# VALVEBOARD_ValveDrive2.net
KiCad netlist of a schematic drawn in Altium Designer
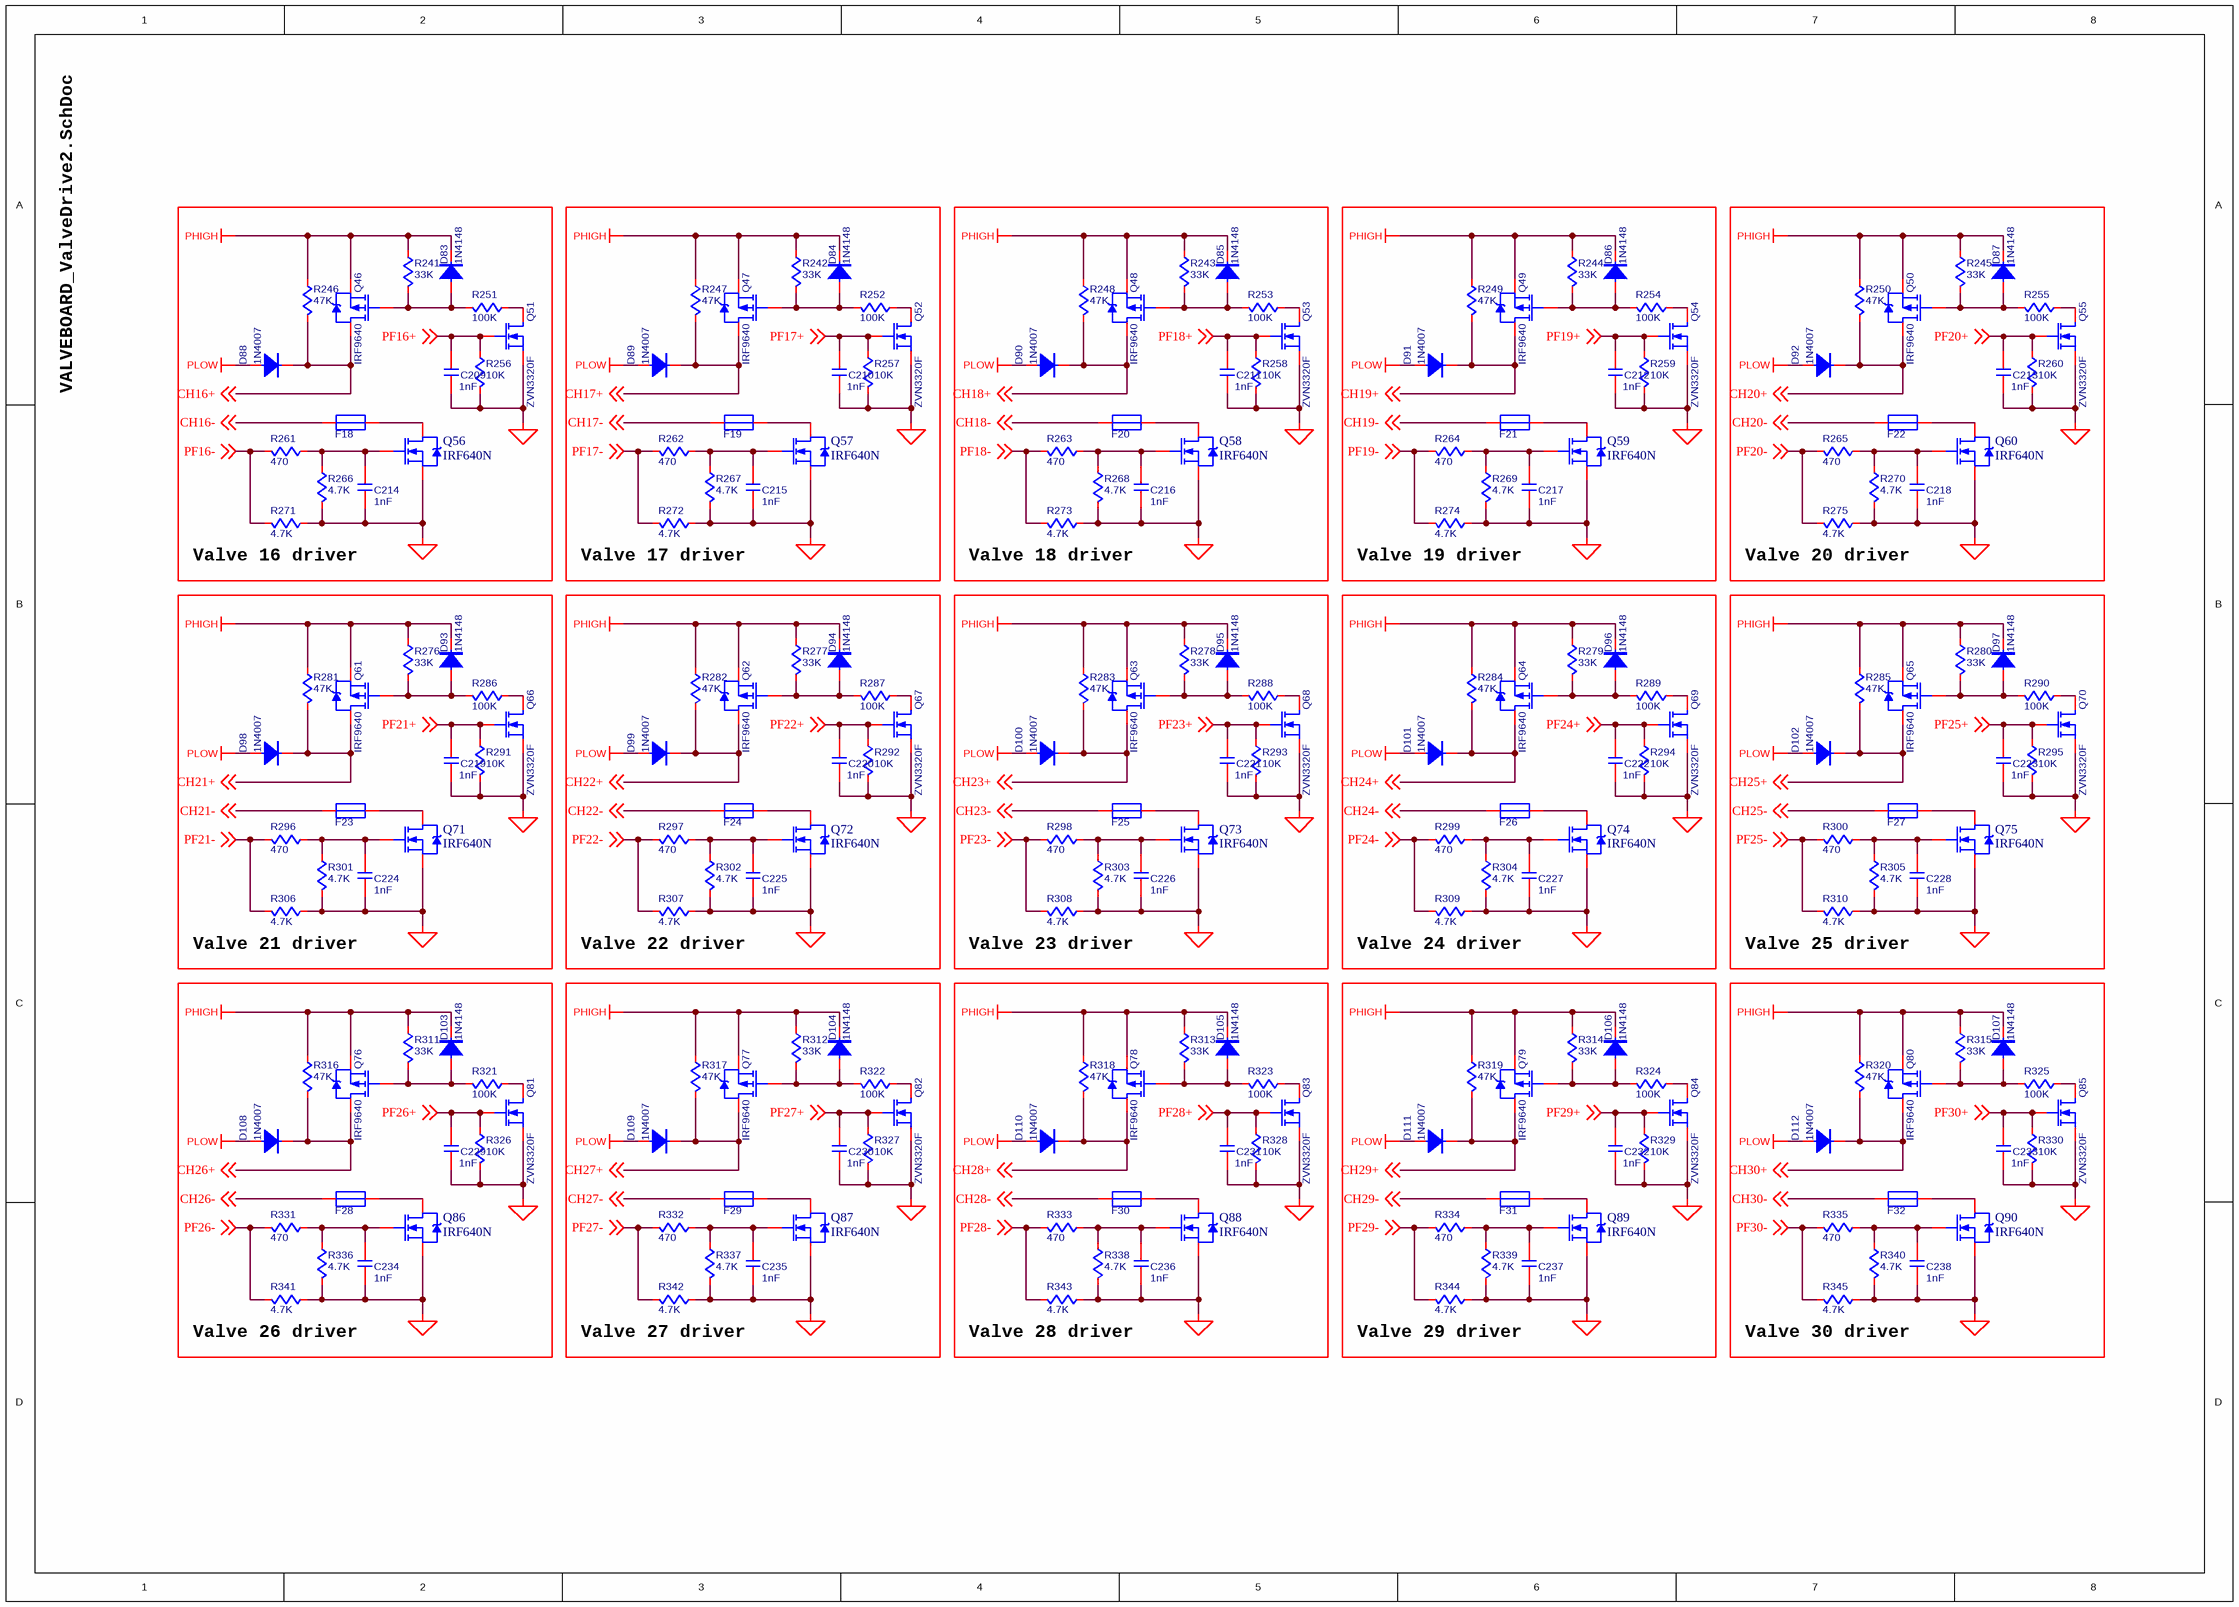
[diagram p0: VALVEBOARD_ValveDrive2.SchDoc]

(export (version "E")
  (design (tool "Eeschema 10.0.6"))
  (components
    (comp (ref "C209")
      (value "1nF")
      (footprint "zynq:C0603")
      (fields (field (name "VOLTAGE") "25V") (field (name "Comment") "C-NOMO"))
      (libsource (lib "zynq") (part "C-NOMO"))
    )
    (comp (ref "C210")
      (value "1nF")
      (footprint "zynq:C0603")
      (fields (field (name "VOLTAGE") "25V") (field (name "Comment") "C-NOMO"))
      (libsource (lib "zynq") (part "C-NOMO"))
    )
    (comp (ref "C211")
      (value "1nF")
      (footprint "zynq:C0603")
      (fields (field (name "VOLTAGE") "25V") (field (name "Comment") "C-NOMO"))
      (libsource (lib "zynq") (part "C-NOMO"))
    )
    (comp (ref "C212")
      (value "1nF")
      (footprint "zynq:C0603")
      (fields (field (name "VOLTAGE") "25V") (field (name "Comment") "C-NOMO"))
      (libsource (lib "zynq") (part "C-NOMO"))
    )
    (comp (ref "C213")
      (value "1nF")
      (footprint "zynq:C0603")
      (fields (field (name "VOLTAGE") "25V") (field (name "Comment") "C-NOMO"))
      (libsource (lib "zynq") (part "C-NOMO"))
    )
    (comp (ref "C214")
      (value "1nF")
      (footprint "zynq:C0603")
      (fields (field (name "VOLTAGE") "25V") (field (name "Comment") "C-NOMO"))
      (libsource (lib "zynq") (part "C-NOMO"))
    )
    (comp (ref "C215")
      (value "1nF")
      (footprint "zynq:C0603")
      (fields (field (name "VOLTAGE") "25V") (field (name "Comment") "C-NOMO"))
      (libsource (lib "zynq") (part "C-NOMO"))
    )
    (comp (ref "C216")
      (value "1nF")
      (footprint "zynq:C0603")
      (fields (field (name "VOLTAGE") "25V") (field (name "Comment") "C-NOMO"))
      (libsource (lib "zynq") (part "C-NOMO"))
    )
    (comp (ref "C217")
      (value "1nF")
      (footprint "zynq:C0603")
      (fields (field (name "VOLTAGE") "25V") (field (name "Comment") "C-NOMO"))
      (libsource (lib "zynq") (part "C-NOMO"))
    )
    (comp (ref "C218")
      (value "1nF")
      (footprint "zynq:C0603")
      (fields (field (name "VOLTAGE") "25V") (field (name "Comment") "C-NOMO"))
      (libsource (lib "zynq") (part "C-NOMO"))
    )
    (comp (ref "C219")
      (value "1nF")
      (footprint "zynq:C0603")
      (fields (field (name "VOLTAGE") "25V") (field (name "Comment") "C-NOMO"))
      (libsource (lib "zynq") (part "C-NOMO"))
    )
    (comp (ref "C220")
      (value "1nF")
      (footprint "zynq:C0603")
      (fields (field (name "VOLTAGE") "25V") (field (name "Comment") "C-NOMO"))
      (libsource (lib "zynq") (part "C-NOMO"))
    )
    (comp (ref "C221")
      (value "1nF")
      (footprint "zynq:C0603")
      (fields (field (name "VOLTAGE") "25V") (field (name "Comment") "C-NOMO"))
      (libsource (lib "zynq") (part "C-NOMO"))
    )
    (comp (ref "C222")
      (value "1nF")
      (footprint "zynq:C0603")
      (fields (field (name "VOLTAGE") "25V") (field (name "Comment") "C-NOMO"))
      (libsource (lib "zynq") (part "C-NOMO"))
    )
    (comp (ref "C223")
      (value "1nF")
      (footprint "zynq:C0603")
      (fields (field (name "VOLTAGE") "25V") (field (name "Comment") "C-NOMO"))
      (libsource (lib "zynq") (part "C-NOMO"))
    )
    (comp (ref "C224")
      (value "1nF")
      (footprint "zynq:C0603")
      (fields (field (name "VOLTAGE") "25V") (field (name "Comment") "C-NOMO"))
      (libsource (lib "zynq") (part "C-NOMO"))
    )
    (comp (ref "C225")
      (value "1nF")
      (footprint "zynq:C0603")
      (fields (field (name "VOLTAGE") "25V") (field (name "Comment") "C-NOMO"))
      (libsource (lib "zynq") (part "C-NOMO"))
    )
    (comp (ref "C226")
      (value "1nF")
      (footprint "zynq:C0603")
      (fields (field (name "VOLTAGE") "25V") (field (name "Comment") "C-NOMO"))
      (libsource (lib "zynq") (part "C-NOMO"))
    )
    (comp (ref "C227")
      (value "1nF")
      (footprint "zynq:C0603")
      (fields (field (name "VOLTAGE") "25V") (field (name "Comment") "C-NOMO"))
      (libsource (lib "zynq") (part "C-NOMO"))
    )
    (comp (ref "C228")
      (value "1nF")
      (footprint "zynq:C0603")
      (fields (field (name "VOLTAGE") "25V") (field (name "Comment") "C-NOMO"))
      (libsource (lib "zynq") (part "C-NOMO"))
    )
    (comp (ref "C229")
      (value "1nF")
      (footprint "zynq:C0603")
      (fields (field (name "VOLTAGE") "25V") (field (name "Comment") "C-NOMO"))
      (libsource (lib "zynq") (part "C-NOMO"))
    )
    (comp (ref "C230")
      (value "1nF")
      (footprint "zynq:C0603")
      (fields (field (name "VOLTAGE") "25V") (field (name "Comment") "C-NOMO"))
      (libsource (lib "zynq") (part "C-NOMO"))
    )
    (comp (ref "C231")
      (value "1nF")
      (footprint "zynq:C0603")
      (fields (field (name "VOLTAGE") "25V") (field (name "Comment") "C-NOMO"))
      (libsource (lib "zynq") (part "C-NOMO"))
    )
    (comp (ref "C232")
      (value "1nF")
      (footprint "zynq:C0603")
      (fields (field (name "VOLTAGE") "25V") (field (name "Comment") "C-NOMO"))
      (libsource (lib "zynq") (part "C-NOMO"))
    )
    (comp (ref "C233")
      (value "1nF")
      (footprint "zynq:C0603")
      (fields (field (name "VOLTAGE") "25V") (field (name "Comment") "C-NOMO"))
      (libsource (lib "zynq") (part "C-NOMO"))
    )
    (comp (ref "C234")
      (value "1nF")
      (footprint "zynq:C0603")
      (fields (field (name "VOLTAGE") "25V") (field (name "Comment") "C-NOMO"))
      (libsource (lib "zynq") (part "C-NOMO"))
    )
    (comp (ref "C235")
      (value "1nF")
      (footprint "zynq:C0603")
      (fields (field (name "VOLTAGE") "25V") (field (name "Comment") "C-NOMO"))
      (libsource (lib "zynq") (part "C-NOMO"))
    )
    (comp (ref "C236")
      (value "1nF")
      (footprint "zynq:C0603")
      (fields (field (name "VOLTAGE") "25V") (field (name "Comment") "C-NOMO"))
      (libsource (lib "zynq") (part "C-NOMO"))
    )
    (comp (ref "C237")
      (value "1nF")
      (footprint "zynq:C0603")
      (fields (field (name "VOLTAGE") "25V") (field (name "Comment") "C-NOMO"))
      (libsource (lib "zynq") (part "C-NOMO"))
    )
    (comp (ref "C238")
      (value "1nF")
      (footprint "zynq:C0603")
      (fields (field (name "VOLTAGE") "25V") (field (name "Comment") "C-NOMO"))
      (libsource (lib "zynq") (part "C-NOMO"))
    )
    (comp (ref "D83") (value "1N4148") (footprint "sod-123") (libsource (lib "") (part "DIOD1_1")))
    (comp (ref "D84") (value "1N4148") (footprint "sod-123") (libsource (lib "") (part "DIOD1_1")))
    (comp (ref "D85") (value "1N4148") (footprint "sod-123") (libsource (lib "") (part "DIOD1_1")))
    (comp (ref "D86") (value "1N4148") (footprint "sod-123") (libsource (lib "") (part "DIOD1_1")))
    (comp (ref "D87") (value "1N4148") (footprint "sod-123") (libsource (lib "") (part "DIOD1_1")))
    (comp (ref "D88") (value "1N4007") (footprint "zynq:1N4148") (libsource (lib "zynq") (part "DIOD1")))
    (comp (ref "D89") (value "1N4007") (footprint "zynq:1N4148") (libsource (lib "zynq") (part "DIOD1")))
    (comp (ref "D90") (value "1N4007") (footprint "zynq:1N4148") (libsource (lib "zynq") (part "DIOD1")))
    (comp (ref "D91") (value "1N4007") (footprint "zynq:1N4148") (libsource (lib "zynq") (part "DIOD1")))
    (comp (ref "D92") (value "1N4007") (footprint "zynq:1N4148") (libsource (lib "zynq") (part "DIOD1")))
    (comp (ref "D93") (value "1N4148") (footprint "sod-123") (libsource (lib "") (part "DIOD1_1")))
    (comp (ref "D94") (value "1N4148") (footprint "sod-123") (libsource (lib "") (part "DIOD1_1")))
    (comp (ref "D95") (value "1N4148") (footprint "sod-123") (libsource (lib "") (part "DIOD1_1")))
    (comp (ref "D96") (value "1N4148") (footprint "sod-123") (libsource (lib "") (part "DIOD1_1")))
    (comp (ref "D97") (value "1N4148") (footprint "sod-123") (libsource (lib "") (part "DIOD1_1")))
    (comp (ref "D98") (value "1N4007") (footprint "zynq:1N4148") (libsource (lib "zynq") (part "DIOD1")))
    (comp (ref "D99") (value "1N4007") (footprint "zynq:1N4148") (libsource (lib "zynq") (part "DIOD1")))
    (comp (ref "D100") (value "1N4007") (footprint "zynq:1N4148") (libsource (lib "zynq") (part "DIOD1")))
    (comp (ref "D101") (value "1N4007") (footprint "zynq:1N4148") (libsource (lib "zynq") (part "DIOD1")))
    (comp (ref "D102") (value "1N4007") (footprint "zynq:1N4148") (libsource (lib "zynq") (part "DIOD1")))
    (comp (ref "D103") (value "1N4148") (footprint "sod-123") (libsource (lib "") (part "DIOD1_1")))
    (comp (ref "D104") (value "1N4148") (footprint "sod-123") (libsource (lib "") (part "DIOD1_1")))
    (comp (ref "D105") (value "1N4148") (footprint "sod-123") (libsource (lib "") (part "DIOD1_1")))
    (comp (ref "D106") (value "1N4148") (footprint "sod-123") (libsource (lib "") (part "DIOD1_1")))
    (comp (ref "D107") (value "1N4148") (footprint "SOD-123") (libsource (lib "") (part "DIOD1_1")))
    (comp (ref "D108") (value "1N4007") (footprint "zynq:1N4148") (libsource (lib "zynq") (part "DIOD1")))
    (comp (ref "D109") (value "1N4007") (footprint "zynq:1N4148") (libsource (lib "zynq") (part "DIOD1")))
    (comp (ref "D110") (value "1N4007") (footprint "zynq:1N4148") (libsource (lib "zynq") (part "DIOD1")))
    (comp (ref "D111") (value "1N4007") (footprint "zynq:1N4148") (libsource (lib "zynq") (part "DIOD1")))
    (comp (ref "D112") (value "1N4007") (footprint "zynq:1N4148") (libsource (lib "zynq") (part "DIOD1")))
    (comp (ref "F18") (value "F50") (footprint "zynq:F-TH") (libsource (lib "zynq") (part "F50")))
    (comp (ref "F19") (value "F50") (footprint "zynq:F-TH") (libsource (lib "zynq") (part "F50")))
    (comp (ref "F20") (value "F50") (footprint "zynq:F-TH") (libsource (lib "zynq") (part "F50")))
    (comp (ref "F21") (value "F50") (footprint "zynq:F-TH") (libsource (lib "zynq") (part "F50")))
    (comp (ref "F22") (value "F50") (footprint "zynq:F-TH") (libsource (lib "zynq") (part "F50")))
    (comp (ref "F23") (value "F50") (footprint "zynq:F-TH") (libsource (lib "zynq") (part "F50")))
    (comp (ref "F24") (value "F50") (footprint "zynq:F-TH") (libsource (lib "zynq") (part "F50")))
    (comp (ref "F25") (value "F50") (footprint "zynq:F-TH") (libsource (lib "zynq") (part "F50")))
    (comp (ref "F26") (value "F50") (footprint "zynq:F-TH") (libsource (lib "zynq") (part "F50")))
    (comp (ref "F27") (value "F50") (footprint "zynq:F-TH") (libsource (lib "zynq") (part "F50")))
    (comp (ref "F28") (value "F50") (footprint "zynq:F-TH") (libsource (lib "zynq") (part "F50")))
    (comp (ref "F29") (value "F50") (footprint "zynq:F-TH") (libsource (lib "zynq") (part "F50")))
    (comp (ref "F30") (value "F50") (footprint "zynq:F-TH") (libsource (lib "zynq") (part "F50")))
    (comp (ref "F31") (value "F50") (footprint "zynq:F-TH") (libsource (lib "zynq") (part "F50")))
    (comp (ref "F32") (value "F50") (footprint "zynq:F-TH") (libsource (lib "zynq") (part "F50")))
    (comp (ref "Q46")
      (value "IRF9640")
      (footprint "TO-220AB")
      (description "P-Channel Power MOSFET")
      (fields (field (name "PUBLISHER") "Altium Limited"))
      (libsource (lib "zynq") (part "IRF9640"))
    )
    (comp (ref "Q47")
      (value "IRF9640")
      (footprint "TO-220AB")
      (description "P-Channel Power MOSFET")
      (fields (field (name "PUBLISHER") "Altium Limited"))
      (libsource (lib "zynq") (part "IRF9640"))
    )
    (comp (ref "Q48")
      (value "IRF9640")
      (footprint "TO-220AB")
      (description "P-Channel Power MOSFET")
      (fields (field (name "PUBLISHER") "Altium Limited"))
      (libsource (lib "zynq") (part "IRF9640"))
    )
    (comp (ref "Q49")
      (value "IRF9640")
      (footprint "TO-220AB")
      (description "P-Channel Power MOSFET")
      (fields (field (name "PUBLISHER") "Altium Limited"))
      (libsource (lib "zynq") (part "IRF9640"))
    )
    (comp (ref "Q50")
      (value "IRF9640")
      (footprint "TO-220AB")
      (description "P-Channel Power MOSFET")
      (fields (field (name "PUBLISHER") "Altium Limited"))
      (libsource (lib "zynq") (part "IRF9640"))
    )
    (comp (ref "Q51")
      (value "ZVN3320F")
      (footprint "zynq:ZVN3320F")
      (description "N-Channel MOSFET")
      (fields (field (name "PUBLISHER") "Altium Limited"))
      (libsource (lib "zynq") (part "ZVN3320F"))
    )
    (comp (ref "Q52")
      (value "ZVN3320F")
      (footprint "zynq:ZVN3320F")
      (description "N-Channel MOSFET")
      (fields (field (name "PUBLISHER") "Altium Limited"))
      (libsource (lib "zynq") (part "ZVN3320F"))
    )
    (comp (ref "Q53")
      (value "ZVN3320F")
      (footprint "zynq:ZVN3320F")
      (description "N-Channel MOSFET")
      (fields (field (name "PUBLISHER") "Altium Limited"))
      (libsource (lib "zynq") (part "ZVN3320F"))
    )
    (comp (ref "Q54")
      (value "ZVN3320F")
      (footprint "zynq:ZVN3320F")
      (description "N-Channel MOSFET")
      (fields (field (name "PUBLISHER") "Altium Limited"))
      (libsource (lib "zynq") (part "ZVN3320F"))
    )
    (comp (ref "Q55")
      (value "ZVN3320F")
      (footprint "zynq:ZVN3320F")
      (description "N-Channel MOSFET")
      (fields (field (name "PUBLISHER") "Altium Limited"))
      (libsource (lib "zynq") (part "ZVN3320F"))
    )
    (comp (ref "Q56")
      (value "IRF640N")
      (footprint "zynq:TO-220AB")
      (description "N-Channel Power MOSFET")
      (fields (field (name "PUBLISHER") "Altium Limited"))
      (libsource (lib "zynq") (part "IRF640N"))
    )
    (comp (ref "Q57")
      (value "IRF640N")
      (footprint "zynq:TO-220AB")
      (description "N-Channel Power MOSFET")
      (fields (field (name "PUBLISHER") "Altium Limited"))
      (libsource (lib "zynq") (part "IRF640N"))
    )
    (comp (ref "Q58")
      (value "IRF640N")
      (footprint "zynq:TO-220AB")
      (description "N-Channel Power MOSFET")
      (fields (field (name "PUBLISHER") "Altium Limited"))
      (libsource (lib "zynq") (part "IRF640N"))
    )
    (comp (ref "Q59")
      (value "IRF640N")
      (footprint "zynq:TO-220AB")
      (description "N-Channel Power MOSFET")
      (fields (field (name "PUBLISHER") "Altium Limited"))
      (libsource (lib "zynq") (part "IRF640N"))
    )
    (comp (ref "Q60")
      (value "IRF640N")
      (footprint "zynq:TO-220AB")
      (description "N-Channel Power MOSFET")
      (fields (field (name "PUBLISHER") "Altium Limited"))
      (libsource (lib "zynq") (part "IRF640N"))
    )
    (comp (ref "Q61")
      (value "IRF9640")
      (footprint "TO-220AB")
      (description "P-Channel Power MOSFET")
      (fields (field (name "PUBLISHER") "Altium Limited"))
      (libsource (lib "zynq") (part "IRF9640"))
    )
    (comp (ref "Q62")
      (value "IRF9640")
      (footprint "TO-220AB")
      (description "P-Channel Power MOSFET")
      (fields (field (name "PUBLISHER") "Altium Limited"))
      (libsource (lib "zynq") (part "IRF9640"))
    )
    (comp (ref "Q63")
      (value "IRF9640")
      (footprint "TO-220AB")
      (description "P-Channel Power MOSFET")
      (fields (field (name "PUBLISHER") "Altium Limited"))
      (libsource (lib "zynq") (part "IRF9640"))
    )
    (comp (ref "Q64")
      (value "IRF9640")
      (footprint "TO-220AB")
      (description "P-Channel Power MOSFET")
      (fields (field (name "PUBLISHER") "Altium Limited"))
      (libsource (lib "zynq") (part "IRF9640"))
    )
    (comp (ref "Q65")
      (value "IRF9640")
      (footprint "TO-220AB")
      (description "P-Channel Power MOSFET")
      (fields (field (name "PUBLISHER") "Altium Limited"))
      (libsource (lib "zynq") (part "IRF9640"))
    )
    (comp (ref "Q66")
      (value "ZVN3320F")
      (footprint "zynq:ZVN3320F")
      (description "N-Channel MOSFET")
      (fields (field (name "PUBLISHER") "Altium Limited"))
      (libsource (lib "zynq") (part "ZVN3320F"))
    )
    (comp (ref "Q67")
      (value "ZVN3320F")
      (footprint "zynq:ZVN3320F")
      (description "N-Channel MOSFET")
      (fields (field (name "PUBLISHER") "Altium Limited"))
      (libsource (lib "zynq") (part "ZVN3320F"))
    )
    (comp (ref "Q68")
      (value "ZVN3320F")
      (footprint "zynq:ZVN3320F")
      (description "N-Channel MOSFET")
      (fields (field (name "PUBLISHER") "Altium Limited"))
      (libsource (lib "zynq") (part "ZVN3320F"))
    )
    (comp (ref "Q69")
      (value "ZVN3320F")
      (footprint "zynq:ZVN3320F")
      (description "N-Channel MOSFET")
      (fields (field (name "PUBLISHER") "Altium Limited"))
      (libsource (lib "zynq") (part "ZVN3320F"))
    )
    (comp (ref "Q70")
      (value "ZVN3320F")
      (footprint "zynq:ZVN3320F")
      (description "N-Channel MOSFET")
      (fields (field (name "PUBLISHER") "Altium Limited"))
      (libsource (lib "zynq") (part "ZVN3320F"))
    )
    (comp (ref "Q71")
      (value "IRF640N")
      (footprint "zynq:TO-220AB")
      (description "N-Channel Power MOSFET")
      (fields (field (name "PUBLISHER") "Altium Limited"))
      (libsource (lib "zynq") (part "IRF640N"))
    )
    (comp (ref "Q72")
      (value "IRF640N")
      (footprint "zynq:TO-220AB")
      (description "N-Channel Power MOSFET")
      (fields (field (name "PUBLISHER") "Altium Limited"))
      (libsource (lib "zynq") (part "IRF640N"))
    )
    (comp (ref "Q73")
      (value "IRF640N")
      (footprint "zynq:TO-220AB")
      (description "N-Channel Power MOSFET")
      (fields (field (name "PUBLISHER") "Altium Limited"))
      (libsource (lib "zynq") (part "IRF640N"))
    )
    (comp (ref "Q74")
      (value "IRF640N")
      (footprint "zynq:TO-220AB")
      (description "N-Channel Power MOSFET")
      (fields (field (name "PUBLISHER") "Altium Limited"))
      (libsource (lib "zynq") (part "IRF640N"))
    )
    (comp (ref "Q75")
      (value "IRF640N")
      (footprint "zynq:TO-220AB")
      (description "N-Channel Power MOSFET")
      (fields (field (name "PUBLISHER") "Altium Limited"))
      (libsource (lib "zynq") (part "IRF640N"))
    )
    (comp (ref "Q76")
      (value "IRF9640")
      (footprint "TO-220AB")
      (description "P-Channel Power MOSFET")
      (fields (field (name "PUBLISHER") "Altium Limited"))
      (libsource (lib "zynq") (part "IRF9640"))
    )
    (comp (ref "Q77")
      (value "IRF9640")
      (footprint "TO-220AB")
      (description "P-Channel Power MOSFET")
      (fields (field (name "PUBLISHER") "Altium Limited"))
      (libsource (lib "zynq") (part "IRF9640"))
    )
    (comp (ref "Q78")
      (value "IRF9640")
      (footprint "TO-220AB")
      (description "P-Channel Power MOSFET")
      (fields (field (name "PUBLISHER") "Altium Limited"))
      (libsource (lib "zynq") (part "IRF9640"))
    )
    (comp (ref "Q79")
      (value "IRF9640")
      (footprint "TO-220AB")
      (description "P-Channel Power MOSFET")
      (fields (field (name "PUBLISHER") "Altium Limited"))
      (libsource (lib "zynq") (part "IRF9640"))
    )
    (comp (ref "Q80")
      (value "IRF9640")
      (footprint "TO-220AB")
      (description "P-Channel Power MOSFET")
      (fields (field (name "PUBLISHER") "Altium Limited"))
      (libsource (lib "zynq") (part "IRF9640"))
    )
    (comp (ref "Q81")
      (value "ZVN3320F")
      (footprint "zynq:ZVN3320F")
      (description "N-Channel MOSFET")
      (fields (field (name "PUBLISHER") "Altium Limited"))
      (libsource (lib "zynq") (part "ZVN3320F"))
    )
    (comp (ref "Q82")
      (value "ZVN3320F")
      (footprint "zynq:ZVN3320F")
      (description "N-Channel MOSFET")
      (fields (field (name "PUBLISHER") "Altium Limited"))
      (libsource (lib "zynq") (part "ZVN3320F"))
    )
    (comp (ref "Q83")
      (value "ZVN3320F")
      (footprint "zynq:ZVN3320F")
      (description "N-Channel MOSFET")
      (fields (field (name "PUBLISHER") "Altium Limited"))
      (libsource (lib "zynq") (part "ZVN3320F"))
    )
    (comp (ref "Q84")
      (value "ZVN3320F")
      (footprint "zynq:ZVN3320F")
      (description "N-Channel MOSFET")
      (fields (field (name "PUBLISHER") "Altium Limited"))
      (libsource (lib "zynq") (part "ZVN3320F"))
    )
    (comp (ref "Q85")
      (value "ZVN3320F")
      (footprint "zynq:ZVN3320F")
      (description "N-Channel MOSFET")
      (fields (field (name "PUBLISHER") "Altium Limited"))
      (libsource (lib "zynq") (part "ZVN3320F"))
    )
    (comp (ref "Q86")
      (value "IRF640N")
      (footprint "zynq:TO-220AB")
      (description "N-Channel Power MOSFET")
      (fields (field (name "PUBLISHER") "Altium Limited"))
      (libsource (lib "zynq") (part "IRF640N"))
    )
    (comp (ref "Q87")
      (value "IRF640N")
      (footprint "zynq:TO-220AB")
      (description "N-Channel Power MOSFET")
      (fields (field (name "PUBLISHER") "Altium Limited"))
      (libsource (lib "zynq") (part "IRF640N"))
    )
    (comp (ref "Q88")
      (value "IRF640N")
      (footprint "zynq:TO-220AB")
      (description "N-Channel Power MOSFET")
      (fields (field (name "PUBLISHER") "Altium Limited"))
      (libsource (lib "zynq") (part "IRF640N"))
    )
    (comp (ref "Q89")
      (value "IRF640N")
      (footprint "zynq:TO-220AB")
      (description "N-Channel Power MOSFET")
      (fields (field (name "PUBLISHER") "Altium Limited"))
      (libsource (lib "zynq") (part "IRF640N"))
    )
    (comp (ref "Q90")
      (value "IRF640N")
      (footprint "zynq:TO-220AB")
      (description "N-Channel Power MOSFET")
      (fields (field (name "PUBLISHER") "Altium Limited"))
      (libsource (lib "zynq") (part "IRF640N"))
    )
    (comp (ref "R241")
      (value "33K")
      (footprint "zynq:R0603")
      (fields (field (name "Comment") "R"))
      (libsource (lib "zynq") (part "R"))
    )
    (comp (ref "R242")
      (value "33K")
      (footprint "zynq:R0603")
      (fields (field (name "Comment") "R"))
      (libsource (lib "zynq") (part "R"))
    )
    (comp (ref "R243")
      (value "33K")
      (footprint "zynq:R0603")
      (fields (field (name "Comment") "R"))
      (libsource (lib "zynq") (part "R"))
    )
    (comp (ref "R244")
      (value "33K")
      (footprint "zynq:R0603")
      (fields (field (name "Comment") "R"))
      (libsource (lib "zynq") (part "R"))
    )
    (comp (ref "R245")
      (value "33K")
      (footprint "zynq:R0603")
      (fields (field (name "Comment") "R"))
      (libsource (lib "zynq") (part "R"))
    )
    (comp (ref "R246")
      (value "47K")
      (footprint "R2512")
      (fields (field (name "Comment") "R"))
      (libsource (lib "zynq") (part "R"))
    )
    (comp (ref "R247")
      (value "47K")
      (footprint "R2512")
      (fields (field (name "Comment") "R"))
      (libsource (lib "zynq") (part "R"))
    )
    (comp (ref "R248")
      (value "47K")
      (footprint "R2512")
      (fields (field (name "Comment") "R"))
      (libsource (lib "zynq") (part "R"))
    )
    (comp (ref "R249")
      (value "47K")
      (footprint "R2512")
      (fields (field (name "Comment") "R"))
      (libsource (lib "zynq") (part "R"))
    )
    (comp (ref "R250")
      (value "47K")
      (footprint "R2512")
      (fields (field (name "Comment") "R"))
      (libsource (lib "zynq") (part "R"))
    )
    (comp (ref "R251")
      (value "100K")
      (footprint "zynq:R0603")
      (fields (field (name "Comment") "R"))
      (libsource (lib "zynq") (part "R"))
    )
    (comp (ref "R252")
      (value "100K")
      (footprint "zynq:R0603")
      (fields (field (name "Comment") "R"))
      (libsource (lib "zynq") (part "R"))
    )
    (comp (ref "R253")
      (value "100K")
      (footprint "zynq:R0603")
      (fields (field (name "Comment") "R"))
      (libsource (lib "zynq") (part "R"))
    )
    (comp (ref "R254")
      (value "100K")
      (footprint "zynq:R0603")
      (fields (field (name "Comment") "R"))
      (libsource (lib "zynq") (part "R"))
    )
    (comp (ref "R255")
      (value "100K")
      (footprint "zynq:R0603")
      (fields (field (name "Comment") "R"))
      (libsource (lib "zynq") (part "R"))
    )
    (comp (ref "R256")
      (value "10K")
      (footprint "zynq:R0603")
      (fields (field (name "Comment") "R"))
      (libsource (lib "zynq") (part "R"))
    )
    (comp (ref "R257")
      (value "10K")
      (footprint "zynq:R0603")
      (fields (field (name "Comment") "R"))
      (libsource (lib "zynq") (part "R"))
    )
    (comp (ref "R258")
      (value "10K")
      (footprint "zynq:R0603")
      (fields (field (name "Comment") "R"))
      (libsource (lib "zynq") (part "R"))
    )
    (comp (ref "R259")
      (value "10K")
      (footprint "zynq:R0603")
      (fields (field (name "Comment") "R"))
      (libsource (lib "zynq") (part "R"))
    )
    (comp (ref "R260")
      (value "10K")
      (footprint "zynq:R0603")
      (fields (field (name "Comment") "R"))
      (libsource (lib "zynq") (part "R"))
    )
    (comp (ref "R261")
      (value "470")
      (footprint "zynq:R0402")
      (fields (field (name "Comment") "R"))
      (libsource (lib "zynq") (part "R"))
    )
    (comp (ref "R262")
      (value "470")
      (footprint "zynq:R0402")
      (fields (field (name "Comment") "R"))
      (libsource (lib "zynq") (part "R"))
    )
    (comp (ref "R263")
      (value "470")
      (footprint "zynq:R0402")
      (fields (field (name "Comment") "R"))
      (libsource (lib "zynq") (part "R"))
    )
    (comp (ref "R264")
      (value "470")
      (footprint "zynq:R0402")
      (fields (field (name "Comment") "R"))
      (libsource (lib "zynq") (part "R"))
    )
    (comp (ref "R265")
      (value "470")
      (footprint "zynq:R0402")
      (fields (field (name "Comment") "R"))
      (libsource (lib "zynq") (part "R"))
    )
    (comp (ref "R266")
      (value "4.7K")
      (footprint "zynq:R0402")
      (fields (field (name "Comment") "R"))
      (libsource (lib "zynq") (part "R"))
    )
    (comp (ref "R267")
      (value "4.7K")
      (footprint "zynq:R0402")
      (fields (field (name "Comment") "R"))
      (libsource (lib "zynq") (part "R"))
    )
    (comp (ref "R268")
      (value "4.7K")
      (footprint "zynq:R0402")
      (fields (field (name "Comment") "R"))
      (libsource (lib "zynq") (part "R"))
    )
    (comp (ref "R269")
      (value "4.7K")
      (footprint "zynq:R0402")
      (fields (field (name "Comment") "R"))
      (libsource (lib "zynq") (part "R"))
    )
    (comp (ref "R270")
      (value "4.7K")
      (footprint "zynq:R0402")
      (fields (field (name "Comment") "R"))
      (libsource (lib "zynq") (part "R"))
    )
    (comp (ref "R271")
      (value "4.7K")
      (footprint "zynq:R0402")
      (fields (field (name "Comment") "R"))
      (libsource (lib "zynq") (part "R"))
    )
    (comp (ref "R272")
      (value "4.7K")
      (footprint "zynq:R0402")
      (fields (field (name "Comment") "R"))
      (libsource (lib "zynq") (part "R"))
    )
    (comp (ref "R273")
      (value "4.7K")
      (footprint "zynq:R0402")
      (fields (field (name "Comment") "R"))
      (libsource (lib "zynq") (part "R"))
    )
    (comp (ref "R274")
      (value "4.7K")
      (footprint "zynq:R0402")
      (fields (field (name "Comment") "R"))
      (libsource (lib "zynq") (part "R"))
    )
    (comp (ref "R275")
      (value "4.7K")
      (footprint "zynq:R0402")
      (fields (field (name "Comment") "R"))
      (libsource (lib "zynq") (part "R"))
    )
    (comp (ref "R276")
      (value "33K")
      (footprint "zynq:R0603")
      (fields (field (name "Comment") "R"))
      (libsource (lib "zynq") (part "R"))
    )
    (comp (ref "R277")
      (value "33K")
      (footprint "zynq:R0603")
      (fields (field (name "Comment") "R"))
      (libsource (lib "zynq") (part "R"))
    )
    (comp (ref "R278")
      (value "33K")
      (footprint "zynq:R0603")
      (fields (field (name "Comment") "R"))
      (libsource (lib "zynq") (part "R"))
    )
    (comp (ref "R279")
      (value "33K")
      (footprint "zynq:R0603")
      (fields (field (name "Comment") "R"))
      (libsource (lib "zynq") (part "R"))
    )
    (comp (ref "R280")
      (value "33K")
      (footprint "zynq:R0603")
      (fields (field (name "Comment") "R"))
      (libsource (lib "zynq") (part "R"))
    )
    (comp (ref "R281")
      (value "47K")
      (footprint "R2512")
      (fields (field (name "Comment") "R"))
      (libsource (lib "zynq") (part "R"))
    )
    (comp (ref "R282")
      (value "47K")
      (footprint "R2512")
      (fields (field (name "Comment") "R"))
      (libsource (lib "zynq") (part "R"))
    )
    (comp (ref "R283")
      (value "47K")
      (footprint "R2512")
      (fields (field (name "Comment") "R"))
      (libsource (lib "zynq") (part "R"))
    )
    (comp (ref "R284")
      (value "47K")
      (footprint "R2512")
      (fields (field (name "Comment") "R"))
      (libsource (lib "zynq") (part "R"))
    )
    (comp (ref "R285")
      (value "47K")
      (footprint "R2512")
      (fields (field (name "Comment") "R"))
      (libsource (lib "zynq") (part "R"))
    )
    (comp (ref "R286")
      (value "100K")
      (footprint "zynq:R0603")
      (fields (field (name "Comment") "R"))
      (libsource (lib "zynq") (part "R"))
    )
    (comp (ref "R287")
      (value "100K")
      (footprint "zynq:R0603")
      (fields (field (name "Comment") "R"))
      (libsource (lib "zynq") (part "R"))
    )
    (comp (ref "R288")
      (value "100K")
      (footprint "zynq:R0603")
      (fields (field (name "Comment") "R"))
      (libsource (lib "zynq") (part "R"))
    )
    (comp (ref "R289")
      (value "100K")
      (footprint "zynq:R0603")
      (fields (field (name "Comment") "R"))
      (libsource (lib "zynq") (part "R"))
    )
    (comp (ref "R290")
      (value "100K")
      (footprint "zynq:R0603")
      (fields (field (name "Comment") "R"))
      (libsource (lib "zynq") (part "R"))
    )
    (comp (ref "R291")
      (value "10K")
      (footprint "zynq:R0603")
      (fields (field (name "Comment") "R"))
      (libsource (lib "zynq") (part "R"))
    )
    (comp (ref "R292")
      (value "10K")
      (footprint "zynq:R0603")
      (fields (field (name "Comment") "R"))
      (libsource (lib "zynq") (part "R"))
    )
    (comp (ref "R293")
      (value "10K")
      (footprint "zynq:R0603")
      (fields (field (name "Comment") "R"))
      (libsource (lib "zynq") (part "R"))
    )
    (comp (ref "R294")
      (value "10K")
      (footprint "zynq:R0603")
      (fields (field (name "Comment") "R"))
      (libsource (lib "zynq") (part "R"))
    )
    (comp (ref "R295")
      (value "10K")
      (footprint "zynq:R0603")
      (fields (field (name "Comment") "R"))
      (libsource (lib "zynq") (part "R"))
    )
    (comp (ref "R296")
      (value "470")
      (footprint "zynq:R0402")
      (fields (field (name "Comment") "R"))
      (libsource (lib "zynq") (part "R"))
    )
    (comp (ref "R297")
      (value "470")
      (footprint "zynq:R0402")
      (fields (field (name "Comment") "R"))
      (libsource (lib "zynq") (part "R"))
    )
    (comp (ref "R298")
      (value "470")
      (footprint "zynq:R0402")
      (fields (field (name "Comment") "R"))
      (libsource (lib "zynq") (part "R"))
    )
    (comp (ref "R299")
      (value "470")
      (footprint "zynq:R0402")
      (fields (field (name "Comment") "R"))
      (libsource (lib "zynq") (part "R"))
    )
    (comp (ref "R300")
      (value "470")
      (footprint "zynq:R0402")
      (fields (field (name "Comment") "R"))
      (libsource (lib "zynq") (part "R"))
    )
    (comp (ref "R301")
      (value "4.7K")
      (footprint "zynq:R0402")
      (fields (field (name "Comment") "R"))
      (libsource (lib "zynq") (part "R"))
    )
    (comp (ref "R302")
      (value "4.7K")
      (footprint "zynq:R0402")
      (fields (field (name "Comment") "R"))
      (libsource (lib "zynq") (part "R"))
    )
    (comp (ref "R303")
      (value "4.7K")
      (footprint "zynq:R0402")
      (fields (field (name "Comment") "R"))
      (libsource (lib "zynq") (part "R"))
    )
    (comp (ref "R304")
      (value "4.7K")
      (footprint "zynq:R0402")
      (fields (field (name "Comment") "R"))
      (libsource (lib "zynq") (part "R"))
    )
    (comp (ref "R305")
      (value "4.7K")
      (footprint "zynq:R0402")
      (fields (field (name "Comment") "R"))
      (libsource (lib "zynq") (part "R"))
    )
    (comp (ref "R306")
      (value "4.7K")
      (footprint "zynq:R0402")
      (fields (field (name "Comment") "R"))
      (libsource (lib "zynq") (part "R"))
    )
    (comp (ref "R307")
      (value "4.7K")
      (footprint "zynq:R0402")
      (fields (field (name "Comment") "R"))
      (libsource (lib "zynq") (part "R"))
    )
    (comp (ref "R308")
      (value "4.7K")
      (footprint "zynq:R0402")
      (fields (field (name "Comment") "R"))
      (libsource (lib "zynq") (part "R"))
    )
    (comp (ref "R309")
      (value "4.7K")
      (footprint "zynq:R0402")
      (fields (field (name "Comment") "R"))
      (libsource (lib "zynq") (part "R"))
    )
    (comp (ref "R310")
      (value "4.7K")
      (footprint "zynq:R0402")
      (fields (field (name "Comment") "R"))
      (libsource (lib "zynq") (part "R"))
    )
    (comp (ref "R311")
      (value "33K")
      (footprint "zynq:R0603")
      (fields (field (name "Comment") "R"))
      (libsource (lib "zynq") (part "R"))
    )
    (comp (ref "R312")
      (value "33K")
      (footprint "zynq:R0603")
      (fields (field (name "Comment") "R"))
      (libsource (lib "zynq") (part "R"))
    )
    (comp (ref "R313")
      (value "33K")
      (footprint "zynq:R0603")
      (fields (field (name "Comment") "R"))
      (libsource (lib "zynq") (part "R"))
    )
    (comp (ref "R314")
      (value "33K")
      (footprint "zynq:R0603")
      (fields (field (name "Comment") "R"))
      (libsource (lib "zynq") (part "R"))
    )
    (comp (ref "R315")
      (value "33K")
      (footprint "zynq:R0603")
      (fields (field (name "Comment") "R"))
      (libsource (lib "zynq") (part "R"))
    )
    (comp (ref "R316")
      (value "47K")
      (footprint "R2512")
      (fields (field (name "Comment") "R"))
      (libsource (lib "zynq") (part "R"))
    )
    (comp (ref "R317")
      (value "47K")
      (footprint "R2512")
      (fields (field (name "Comment") "R"))
      (libsource (lib "zynq") (part "R"))
    )
    (comp (ref "R318")
      (value "47K")
      (footprint "R2512")
      (fields (field (name "Comment") "R"))
      (libsource (lib "zynq") (part "R"))
    )
    (comp (ref "R319")
      (value "47K")
      (footprint "R2512")
      (fields (field (name "Comment") "R"))
      (libsource (lib "zynq") (part "R"))
    )
    (comp (ref "R320")
      (value "47K")
      (footprint "R2512")
      (fields (field (name "Comment") "R"))
      (libsource (lib "zynq") (part "R"))
    )
    (comp (ref "R321")
      (value "100K")
      (footprint "zynq:R0603")
      (fields (field (name "Comment") "R"))
      (libsource (lib "zynq") (part "R"))
    )
    (comp (ref "R322")
      (value "100K")
      (footprint "zynq:R0603")
      (fields (field (name "Comment") "R"))
      (libsource (lib "zynq") (part "R"))
    )
    (comp (ref "R323")
      (value "100K")
      (footprint "zynq:R0603")
      (fields (field (name "Comment") "R"))
      (libsource (lib "zynq") (part "R"))
    )
    (comp (ref "R324")
      (value "100K")
      (footprint "zynq:R0603")
      (fields (field (name "Comment") "R"))
      (libsource (lib "zynq") (part "R"))
    )
    (comp (ref "R325")
      (value "100K")
      (footprint "zynq:R0603")
      (fields (field (name "Comment") "R"))
      (libsource (lib "zynq") (part "R"))
    )
    (comp (ref "R326")
      (value "10K")
      (footprint "zynq:R0603")
      (fields (field (name "Comment") "R"))
      (libsource (lib "zynq") (part "R"))
    )
    (comp (ref "R327")
      (value "10K")
      (footprint "zynq:R0603")
      (fields (field (name "Comment") "R"))
      (libsource (lib "zynq") (part "R"))
    )
    (comp (ref "R328")
      (value "10K")
      (footprint "zynq:R0603")
      (fields (field (name "Comment") "R"))
      (libsource (lib "zynq") (part "R"))
    )
    (comp (ref "R329")
      (value "10K")
      (footprint "zynq:R0603")
      (fields (field (name "Comment") "R"))
      (libsource (lib "zynq") (part "R"))
    )
    (comp (ref "R330")
      (value "10K")
      (footprint "zynq:R0603")
      (fields (field (name "Comment") "R"))
      (libsource (lib "zynq") (part "R"))
    )
    (comp (ref "R331")
      (value "470")
      (footprint "zynq:R0402")
      (fields (field (name "Comment") "R"))
      (libsource (lib "zynq") (part "R"))
    )
    (comp (ref "R332")
      (value "470")
      (footprint "zynq:R0402")
      (fields (field (name "Comment") "R"))
      (libsource (lib "zynq") (part "R"))
    )
    (comp (ref "R333")
      (value "470")
      (footprint "zynq:R0402")
      (fields (field (name "Comment") "R"))
      (libsource (lib "zynq") (part "R"))
    )
    (comp (ref "R334")
      (value "470")
      (footprint "zynq:R0402")
      (fields (field (name "Comment") "R"))
      (libsource (lib "zynq") (part "R"))
    )
    (comp (ref "R335")
      (value "470")
      (footprint "zynq:R0402")
      (fields (field (name "Comment") "R"))
      (libsource (lib "zynq") (part "R"))
    )
    (comp (ref "R336")
      (value "4.7K")
      (footprint "zynq:R0402")
      (fields (field (name "Comment") "R"))
      (libsource (lib "zynq") (part "R"))
    )
    (comp (ref "R337")
      (value "4.7K")
      (footprint "zynq:R0402")
      (fields (field (name "Comment") "R"))
      (libsource (lib "zynq") (part "R"))
    )
    (comp (ref "R338")
      (value "4.7K")
      (footprint "zynq:R0402")
      (fields (field (name "Comment") "R"))
      (libsource (lib "zynq") (part "R"))
    )
    (comp (ref "R339")
      (value "4.7K")
      (footprint "zynq:R0402")
      (fields (field (name "Comment") "R"))
      (libsource (lib "zynq") (part "R"))
    )
    (comp (ref "R340")
      (value "4.7K")
      (footprint "zynq:R0402")
      (fields (field (name "Comment") "R"))
      (libsource (lib "zynq") (part "R"))
    )
    (comp (ref "R341")
      (value "4.7K")
      (footprint "zynq:R0402")
      (fields (field (name "Comment") "R"))
      (libsource (lib "zynq") (part "R"))
    )
    (comp (ref "R342")
      (value "4.7K")
      (footprint "zynq:R0402")
      (fields (field (name "Comment") "R"))
      (libsource (lib "zynq") (part "R"))
    )
    (comp (ref "R343")
      (value "4.7K")
      (footprint "zynq:R0402")
      (fields (field (name "Comment") "R"))
      (libsource (lib "zynq") (part "R"))
    )
    (comp (ref "R344")
      (value "4.7K")
      (footprint "zynq:R0402")
      (fields (field (name "Comment") "R"))
      (libsource (lib "zynq") (part "R"))
    )
    (comp (ref "R345")
      (value "4.7K")
      (footprint "zynq:R0402")
      (fields (field (name "Comment") "R"))
      (libsource (lib "zynq") (part "R"))
    )
  )
  (nets
    (net (code "1") (name "CH16+") (class "Default")
      (node (ref "D88") (pin "1") (pinfunction "1_1") (pintype "passive"))
      (node (ref "Q46") (pin "2") (pinfunction "D_2") (pintype "passive"))
      (node (ref "R246") (pin "1") (pinfunction "1_1") (pintype "passive"))
    )
    (net (code "2") (name "CH16-") (class "Default") (node (ref "F18") (pin "1") (pintype "passive")))
    (net (code "3") (name "CH17+") (class "Default")
      (node (ref "D89") (pin "1") (pinfunction "1_1") (pintype "passive"))
      (node (ref "Q47") (pin "2") (pinfunction "D_2") (pintype "passive"))
      (node (ref "R247") (pin "1") (pinfunction "1_1") (pintype "passive"))
    )
    (net (code "4") (name "CH17-") (class "Default") (node (ref "F19") (pin "1") (pintype "passive")))
    (net (code "5") (name "CH18+") (class "Default")
      (node (ref "D90") (pin "1") (pinfunction "1_1") (pintype "passive"))
      (node (ref "Q48") (pin "2") (pinfunction "D_2") (pintype "passive"))
      (node (ref "R248") (pin "1") (pinfunction "1_1") (pintype "passive"))
    )
    (net (code "6") (name "CH18-") (class "Default") (node (ref "F20") (pin "1") (pintype "passive")))
    (net (code "7") (name "CH19+") (class "Default")
      (node (ref "D91") (pin "1") (pinfunction "1_1") (pintype "passive"))
      (node (ref "Q49") (pin "2") (pinfunction "D_2") (pintype "passive"))
      (node (ref "R249") (pin "1") (pinfunction "1_1") (pintype "passive"))
    )
    (net (code "8") (name "CH19-") (class "Default") (node (ref "F21") (pin "1") (pintype "passive")))
    (net (code "9") (name "CH20+") (class "Default")
      (node (ref "D92") (pin "1") (pinfunction "1_1") (pintype "passive"))
      (node (ref "Q50") (pin "2") (pinfunction "D_2") (pintype "passive"))
      (node (ref "R250") (pin "1") (pinfunction "1_1") (pintype "passive"))
    )
    (net (code "10") (name "CH20-") (class "Default") (node (ref "F22") (pin "1") (pintype "passive")))
    (net (code "11") (name "CH21+") (class "Default")
      (node (ref "D98") (pin "1") (pinfunction "1_1") (pintype "passive"))
      (node (ref "Q61") (pin "2") (pinfunction "D_2") (pintype "passive"))
      (node (ref "R281") (pin "1") (pinfunction "1_1") (pintype "passive"))
    )
    (net (code "12") (name "CH21-") (class "Default") (node (ref "F23") (pin "1") (pintype "passive")))
    (net (code "13") (name "CH22+") (class "Default")
      (node (ref "D99") (pin "1") (pinfunction "1_1") (pintype "passive"))
      (node (ref "Q62") (pin "2") (pinfunction "D_2") (pintype "passive"))
      (node (ref "R282") (pin "1") (pinfunction "1_1") (pintype "passive"))
    )
    (net (code "14") (name "CH22-") (class "Default") (node (ref "F24") (pin "1") (pintype "passive")))
    (net (code "15") (name "CH23+") (class "Default")
      (node (ref "D100") (pin "1") (pinfunction "1_1") (pintype "passive"))
      (node (ref "Q63") (pin "2") (pinfunction "D_2") (pintype "passive"))
      (node (ref "R283") (pin "1") (pinfunction "1_1") (pintype "passive"))
    )
    (net (code "16") (name "CH23-") (class "Default") (node (ref "F25") (pin "1") (pintype "passive")))
    (net (code "17") (name "CH24+") (class "Default")
      (node (ref "D101") (pin "1") (pinfunction "1_1") (pintype "passive"))
      (node (ref "Q64") (pin "2") (pinfunction "D_2") (pintype "passive"))
      (node (ref "R284") (pin "1") (pinfunction "1_1") (pintype "passive"))
    )
    (net (code "18") (name "CH24-") (class "Default") (node (ref "F26") (pin "1") (pintype "passive")))
    (net (code "19") (name "CH25+") (class "Default")
      (node (ref "D102") (pin "1") (pinfunction "1_1") (pintype "passive"))
      (node (ref "Q65") (pin "2") (pinfunction "D_2") (pintype "passive"))
      (node (ref "R285") (pin "1") (pinfunction "1_1") (pintype "passive"))
    )
    (net (code "20") (name "CH25-") (class "Default") (node (ref "F27") (pin "1") (pintype "passive")))
    (net (code "21") (name "CH26+") (class "Default")
      (node (ref "D108") (pin "1") (pinfunction "1_1") (pintype "passive"))
      (node (ref "Q76") (pin "2") (pinfunction "D_2") (pintype "passive"))
      (node (ref "R316") (pin "1") (pinfunction "1_1") (pintype "passive"))
    )
    (net (code "22") (name "CH26-") (class "Default") (node (ref "F28") (pin "1") (pintype "passive")))
    (net (code "23") (name "CH27+") (class "Default")
      (node (ref "D109") (pin "1") (pinfunction "1_1") (pintype "passive"))
      (node (ref "Q77") (pin "2") (pinfunction "D_2") (pintype "passive"))
      (node (ref "R317") (pin "1") (pinfunction "1_1") (pintype "passive"))
    )
    (net (code "24") (name "CH27-") (class "Default") (node (ref "F29") (pin "1") (pintype "passive")))
    (net (code "25") (name "CH28+") (class "Default")
      (node (ref "D110") (pin "1") (pinfunction "1_1") (pintype "passive"))
      (node (ref "Q78") (pin "2") (pinfunction "D_2") (pintype "passive"))
      (node (ref "R318") (pin "1") (pinfunction "1_1") (pintype "passive"))
    )
    (net (code "26") (name "CH28-") (class "Default") (node (ref "F30") (pin "1") (pintype "passive")))
    (net (code "27") (name "CH29+") (class "Default")
      (node (ref "D111") (pin "1") (pinfunction "1_1") (pintype "passive"))
      (node (ref "Q79") (pin "2") (pinfunction "D_2") (pintype "passive"))
      (node (ref "R319") (pin "1") (pinfunction "1_1") (pintype "passive"))
    )
    (net (code "28") (name "CH29-") (class "Default") (node (ref "F31") (pin "1") (pintype "passive")))
    (net (code "29") (name "CH30+") (class "Default")
      (node (ref "D112") (pin "1") (pinfunction "1_1") (pintype "passive"))
      (node (ref "Q80") (pin "2") (pinfunction "D_2") (pintype "passive"))
      (node (ref "R320") (pin "1") (pinfunction "1_1") (pintype "passive"))
    )
    (net (code "30") (name "CH30-") (class "Default") (node (ref "F32") (pin "1") (pintype "passive")))
    (net (code "31") (name "Net-(Q46-G)") (class "Default")
      (node (ref "D83") (pin "2") (pinfunction "2_2") (pintype "passive"))
      (node (ref "Q46") (pin "1") (pinfunction "G_1") (pintype "passive"))
      (node (ref "R241") (pin "1") (pinfunction "1_1") (pintype "passive"))
      (node (ref "R251") (pin "1") (pinfunction "1_1") (pintype "passive"))
    )
    (net (code "32") (name "Net-(Q47-G)") (class "Default")
      (node (ref "D84") (pin "2") (pinfunction "2_2") (pintype "passive"))
      (node (ref "Q47") (pin "1") (pinfunction "G_1") (pintype "passive"))
      (node (ref "R242") (pin "1") (pinfunction "1_1") (pintype "passive"))
      (node (ref "R252") (pin "1") (pinfunction "1_1") (pintype "passive"))
    )
    (net (code "33") (name "Net-(Q48-G)") (class "Default")
      (node (ref "D85") (pin "2") (pinfunction "2_2") (pintype "passive"))
      (node (ref "Q48") (pin "1") (pinfunction "G_1") (pintype "passive"))
      (node (ref "R243") (pin "1") (pinfunction "1_1") (pintype "passive"))
      (node (ref "R253") (pin "1") (pinfunction "1_1") (pintype "passive"))
    )
    (net (code "34") (name "Net-(Q49-G)") (class "Default")
      (node (ref "D86") (pin "2") (pinfunction "2_2") (pintype "passive"))
      (node (ref "Q49") (pin "1") (pinfunction "G_1") (pintype "passive"))
      (node (ref "R244") (pin "1") (pinfunction "1_1") (pintype "passive"))
      (node (ref "R254") (pin "1") (pinfunction "1_1") (pintype "passive"))
    )
    (net (code "35") (name "Net-(Q50-G)") (class "Default")
      (node (ref "D87") (pin "2") (pinfunction "2_2") (pintype "passive"))
      (node (ref "Q50") (pin "1") (pinfunction "G_1") (pintype "passive"))
      (node (ref "R245") (pin "1") (pinfunction "1_1") (pintype "passive"))
      (node (ref "R255") (pin "1") (pinfunction "1_1") (pintype "passive"))
    )
    (net (code "36") (name "Net-(Q51-D)") (class "Default")
      (node (ref "Q51") (pin "1") (pinfunction "D_1") (pintype "passive"))
      (node (ref "R251") (pin "2") (pinfunction "2_2") (pintype "passive"))
    )
    (net (code "37") (name "Net-(Q52-D)") (class "Default")
      (node (ref "Q52") (pin "1") (pinfunction "D_1") (pintype "passive"))
      (node (ref "R252") (pin "2") (pinfunction "2_2") (pintype "passive"))
    )
    (net (code "38") (name "Net-(Q53-D)") (class "Default")
      (node (ref "Q53") (pin "1") (pinfunction "D_1") (pintype "passive"))
      (node (ref "R253") (pin "2") (pinfunction "2_2") (pintype "passive"))
    )
    (net (code "39") (name "Net-(Q54-D)") (class "Default")
      (node (ref "Q54") (pin "1") (pinfunction "D_1") (pintype "passive"))
      (node (ref "R254") (pin "2") (pinfunction "2_2") (pintype "passive"))
    )
    (net (code "40") (name "Net-(Q55-D)") (class "Default")
      (node (ref "Q55") (pin "1") (pinfunction "D_1") (pintype "passive"))
      (node (ref "R255") (pin "2") (pinfunction "2_2") (pintype "passive"))
    )
    (net (code "41") (name "Net-(Q56-D)") (class "Default")
      (node (ref "F18") (pin "2") (pintype "passive"))
      (node (ref "Q56") (pin "2") (pinfunction "D_2") (pintype "passive"))
    )
    (net (code "42") (name "Net-(Q56-G)") (class "Default")
      (node (ref "C214") (pin "2") (pinfunction "2_2") (pintype "passive"))
      (node (ref "Q56") (pin "1") (pinfunction "G_1") (pintype "passive"))
      (node (ref "R261") (pin "2") (pinfunction "2_2") (pintype "passive"))
      (node (ref "R266") (pin "2") (pinfunction "2_2") (pintype "passive"))
    )
    (net (code "43") (name "Net-(Q57-D)") (class "Default")
      (node (ref "F19") (pin "2") (pintype "passive"))
      (node (ref "Q57") (pin "2") (pinfunction "D_2") (pintype "passive"))
    )
    (net (code "44") (name "Net-(Q57-G)") (class "Default")
      (node (ref "C215") (pin "2") (pinfunction "2_2") (pintype "passive"))
      (node (ref "Q57") (pin "1") (pinfunction "G_1") (pintype "passive"))
      (node (ref "R262") (pin "2") (pinfunction "2_2") (pintype "passive"))
      (node (ref "R267") (pin "2") (pinfunction "2_2") (pintype "passive"))
    )
    (net (code "45") (name "Net-(Q58-D)") (class "Default")
      (node (ref "F20") (pin "2") (pintype "passive"))
      (node (ref "Q58") (pin "2") (pinfunction "D_2") (pintype "passive"))
    )
    (net (code "46") (name "Net-(Q58-G)") (class "Default")
      (node (ref "C216") (pin "2") (pinfunction "2_2") (pintype "passive"))
      (node (ref "Q58") (pin "1") (pinfunction "G_1") (pintype "passive"))
      (node (ref "R263") (pin "2") (pinfunction "2_2") (pintype "passive"))
      (node (ref "R268") (pin "2") (pinfunction "2_2") (pintype "passive"))
    )
    (net (code "47") (name "Net-(Q59-D)") (class "Default")
      (node (ref "F21") (pin "2") (pintype "passive"))
      (node (ref "Q59") (pin "2") (pinfunction "D_2") (pintype "passive"))
    )
    (net (code "48") (name "Net-(Q59-G)") (class "Default")
      (node (ref "C217") (pin "2") (pinfunction "2_2") (pintype "passive"))
      (node (ref "Q59") (pin "1") (pinfunction "G_1") (pintype "passive"))
      (node (ref "R264") (pin "2") (pinfunction "2_2") (pintype "passive"))
      (node (ref "R269") (pin "2") (pinfunction "2_2") (pintype "passive"))
    )
    (net (code "49") (name "Net-(Q60-D)") (class "Default")
      (node (ref "F22") (pin "2") (pintype "passive"))
      (node (ref "Q60") (pin "2") (pinfunction "D_2") (pintype "passive"))
    )
    (net (code "50") (name "Net-(Q60-G)") (class "Default")
      (node (ref "C218") (pin "2") (pinfunction "2_2") (pintype "passive"))
      (node (ref "Q60") (pin "1") (pinfunction "G_1") (pintype "passive"))
      (node (ref "R265") (pin "2") (pinfunction "2_2") (pintype "passive"))
      (node (ref "R270") (pin "2") (pinfunction "2_2") (pintype "passive"))
    )
    (net (code "51") (name "Net-(Q61-G)") (class "Default")
      (node (ref "D93") (pin "2") (pinfunction "2_2") (pintype "passive"))
      (node (ref "Q61") (pin "1") (pinfunction "G_1") (pintype "passive"))
      (node (ref "R276") (pin "1") (pinfunction "1_1") (pintype "passive"))
      (node (ref "R286") (pin "1") (pinfunction "1_1") (pintype "passive"))
    )
    (net (code "52") (name "Net-(Q62-G)") (class "Default")
      (node (ref "D94") (pin "2") (pinfunction "2_2") (pintype "passive"))
      (node (ref "Q62") (pin "1") (pinfunction "G_1") (pintype "passive"))
      (node (ref "R277") (pin "1") (pinfunction "1_1") (pintype "passive"))
      (node (ref "R287") (pin "1") (pinfunction "1_1") (pintype "passive"))
    )
    (net (code "53") (name "Net-(Q63-G)") (class "Default")
      (node (ref "D95") (pin "2") (pinfunction "2_2") (pintype "passive"))
      (node (ref "Q63") (pin "1") (pinfunction "G_1") (pintype "passive"))
      (node (ref "R278") (pin "1") (pinfunction "1_1") (pintype "passive"))
      (node (ref "R288") (pin "1") (pinfunction "1_1") (pintype "passive"))
    )
    (net (code "54") (name "Net-(Q64-G)") (class "Default")
      (node (ref "D96") (pin "2") (pinfunction "2_2") (pintype "passive"))
      (node (ref "Q64") (pin "1") (pinfunction "G_1") (pintype "passive"))
      (node (ref "R279") (pin "1") (pinfunction "1_1") (pintype "passive"))
      (node (ref "R289") (pin "1") (pinfunction "1_1") (pintype "passive"))
    )
    (net (code "55") (name "Net-(Q65-G)") (class "Default")
      (node (ref "D97") (pin "2") (pinfunction "2_2") (pintype "passive"))
      (node (ref "Q65") (pin "1") (pinfunction "G_1") (pintype "passive"))
      (node (ref "R280") (pin "1") (pinfunction "1_1") (pintype "passive"))
      (node (ref "R290") (pin "1") (pinfunction "1_1") (pintype "passive"))
    )
    (net (code "56") (name "Net-(Q66-D)") (class "Default")
      (node (ref "Q66") (pin "1") (pinfunction "D_1") (pintype "passive"))
      (node (ref "R286") (pin "2") (pinfunction "2_2") (pintype "passive"))
    )
    (net (code "57") (name "Net-(Q67-D)") (class "Default")
      (node (ref "Q67") (pin "1") (pinfunction "D_1") (pintype "passive"))
      (node (ref "R287") (pin "2") (pinfunction "2_2") (pintype "passive"))
    )
    (net (code "58") (name "Net-(Q68-D)") (class "Default")
      (node (ref "Q68") (pin "1") (pinfunction "D_1") (pintype "passive"))
      (node (ref "R288") (pin "2") (pinfunction "2_2") (pintype "passive"))
    )
    (net (code "59") (name "Net-(Q69-D)") (class "Default")
      (node (ref "Q69") (pin "1") (pinfunction "D_1") (pintype "passive"))
      (node (ref "R289") (pin "2") (pinfunction "2_2") (pintype "passive"))
    )
    (net (code "60") (name "Net-(Q70-D)") (class "Default")
      (node (ref "Q70") (pin "1") (pinfunction "D_1") (pintype "passive"))
      (node (ref "R290") (pin "2") (pinfunction "2_2") (pintype "passive"))
    )
    (net (code "61") (name "Net-(Q71-D)") (class "Default")
      (node (ref "F23") (pin "2") (pintype "passive"))
      (node (ref "Q71") (pin "2") (pinfunction "D_2") (pintype "passive"))
    )
    (net (code "62") (name "Net-(Q71-G)") (class "Default")
      (node (ref "C224") (pin "2") (pinfunction "2_2") (pintype "passive"))
      (node (ref "Q71") (pin "1") (pinfunction "G_1") (pintype "passive"))
      (node (ref "R296") (pin "2") (pinfunction "2_2") (pintype "passive"))
      (node (ref "R301") (pin "2") (pinfunction "2_2") (pintype "passive"))
    )
    (net (code "63") (name "Net-(Q72-D)") (class "Default")
      (node (ref "F24") (pin "2") (pintype "passive"))
      (node (ref "Q72") (pin "2") (pinfunction "D_2") (pintype "passive"))
    )
    (net (code "64") (name "Net-(Q72-G)") (class "Default")
      (node (ref "C225") (pin "2") (pinfunction "2_2") (pintype "passive"))
      (node (ref "Q72") (pin "1") (pinfunction "G_1") (pintype "passive"))
      (node (ref "R297") (pin "2") (pinfunction "2_2") (pintype "passive"))
      (node (ref "R302") (pin "2") (pinfunction "2_2") (pintype "passive"))
    )
    (net (code "65") (name "Net-(Q73-D)") (class "Default")
      (node (ref "F25") (pin "2") (pintype "passive"))
      (node (ref "Q73") (pin "2") (pinfunction "D_2") (pintype "passive"))
    )
    (net (code "66") (name "Net-(Q73-G)") (class "Default")
      (node (ref "C226") (pin "2") (pinfunction "2_2") (pintype "passive"))
      (node (ref "Q73") (pin "1") (pinfunction "G_1") (pintype "passive"))
      (node (ref "R298") (pin "2") (pinfunction "2_2") (pintype "passive"))
      (node (ref "R303") (pin "2") (pinfunction "2_2") (pintype "passive"))
    )
    (net (code "67") (name "Net-(Q74-D)") (class "Default")
      (node (ref "F26") (pin "2") (pintype "passive"))
      (node (ref "Q74") (pin "2") (pinfunction "D_2") (pintype "passive"))
    )
    (net (code "68") (name "Net-(Q74-G)") (class "Default")
      (node (ref "C227") (pin "2") (pinfunction "2_2") (pintype "passive"))
      (node (ref "Q74") (pin "1") (pinfunction "G_1") (pintype "passive"))
      (node (ref "R299") (pin "2") (pinfunction "2_2") (pintype "passive"))
      (node (ref "R304") (pin "2") (pinfunction "2_2") (pintype "passive"))
    )
    (net (code "69") (name "Net-(Q75-D)") (class "Default")
      (node (ref "F27") (pin "2") (pintype "passive"))
      (node (ref "Q75") (pin "2") (pinfunction "D_2") (pintype "passive"))
    )
    (net (code "70") (name "Net-(Q75-G)") (class "Default")
      (node (ref "C228") (pin "2") (pinfunction "2_2") (pintype "passive"))
      (node (ref "Q75") (pin "1") (pinfunction "G_1") (pintype "passive"))
      (node (ref "R300") (pin "2") (pinfunction "2_2") (pintype "passive"))
      (node (ref "R305") (pin "2") (pinfunction "2_2") (pintype "passive"))
    )
    (net (code "71") (name "Net-(Q76-G)") (class "Default")
      (node (ref "D103") (pin "2") (pinfunction "2_2") (pintype "passive"))
      (node (ref "Q76") (pin "1") (pinfunction "G_1") (pintype "passive"))
      (node (ref "R311") (pin "1") (pinfunction "1_1") (pintype "passive"))
      (node (ref "R321") (pin "1") (pinfunction "1_1") (pintype "passive"))
    )
    (net (code "72") (name "Net-(Q77-G)") (class "Default")
      (node (ref "D104") (pin "2") (pinfunction "2_2") (pintype "passive"))
      (node (ref "Q77") (pin "1") (pinfunction "G_1") (pintype "passive"))
      (node (ref "R312") (pin "1") (pinfunction "1_1") (pintype "passive"))
      (node (ref "R322") (pin "1") (pinfunction "1_1") (pintype "passive"))
    )
    (net (code "73") (name "Net-(Q78-G)") (class "Default")
      (node (ref "D105") (pin "2") (pinfunction "2_2") (pintype "passive"))
      (node (ref "Q78") (pin "1") (pinfunction "G_1") (pintype "passive"))
      (node (ref "R313") (pin "1") (pinfunction "1_1") (pintype "passive"))
      (node (ref "R323") (pin "1") (pinfunction "1_1") (pintype "passive"))
    )
    (net (code "74") (name "Net-(Q79-G)") (class "Default")
      (node (ref "D106") (pin "2") (pinfunction "2_2") (pintype "passive"))
      (node (ref "Q79") (pin "1") (pinfunction "G_1") (pintype "passive"))
      (node (ref "R314") (pin "1") (pinfunction "1_1") (pintype "passive"))
      (node (ref "R324") (pin "1") (pinfunction "1_1") (pintype "passive"))
    )
    (net (code "75") (name "Net-(Q80-G)") (class "Default")
      (node (ref "D107") (pin "2") (pinfunction "2_2") (pintype "passive"))
      (node (ref "Q80") (pin "1") (pinfunction "G_1") (pintype "passive"))
      (node (ref "R315") (pin "1") (pinfunction "1_1") (pintype "passive"))
      (node (ref "R325") (pin "1") (pinfunction "1_1") (pintype "passive"))
    )
    (net (code "76") (name "Net-(Q81-D)") (class "Default")
      (node (ref "Q81") (pin "1") (pinfunction "D_1") (pintype "passive"))
      (node (ref "R321") (pin "2") (pinfunction "2_2") (pintype "passive"))
    )
    (net (code "77") (name "Net-(Q82-D)") (class "Default")
      (node (ref "Q82") (pin "1") (pinfunction "D_1") (pintype "passive"))
      (node (ref "R322") (pin "2") (pinfunction "2_2") (pintype "passive"))
    )
    (net (code "78") (name "Net-(Q83-D)") (class "Default")
      (node (ref "Q83") (pin "1") (pinfunction "D_1") (pintype "passive"))
      (node (ref "R323") (pin "2") (pinfunction "2_2") (pintype "passive"))
    )
    (net (code "79") (name "Net-(Q84-D)") (class "Default")
      (node (ref "Q84") (pin "1") (pinfunction "D_1") (pintype "passive"))
      (node (ref "R324") (pin "2") (pinfunction "2_2") (pintype "passive"))
    )
    (net (code "80") (name "Net-(Q85-D)") (class "Default")
      (node (ref "Q85") (pin "1") (pinfunction "D_1") (pintype "passive"))
      (node (ref "R325") (pin "2") (pinfunction "2_2") (pintype "passive"))
    )
    (net (code "81") (name "Net-(Q86-D)") (class "Default")
      (node (ref "F28") (pin "2") (pintype "passive"))
      (node (ref "Q86") (pin "2") (pinfunction "D_2") (pintype "passive"))
    )
    (net (code "82") (name "Net-(Q86-G)") (class "Default")
      (node (ref "C234") (pin "2") (pinfunction "2_2") (pintype "passive"))
      (node (ref "Q86") (pin "1") (pinfunction "G_1") (pintype "passive"))
      (node (ref "R331") (pin "2") (pinfunction "2_2") (pintype "passive"))
      (node (ref "R336") (pin "2") (pinfunction "2_2") (pintype "passive"))
    )
    (net (code "83") (name "Net-(Q87-D)") (class "Default")
      (node (ref "F29") (pin "2") (pintype "passive"))
      (node (ref "Q87") (pin "2") (pinfunction "D_2") (pintype "passive"))
    )
    (net (code "84") (name "Net-(Q87-G)") (class "Default")
      (node (ref "C235") (pin "2") (pinfunction "2_2") (pintype "passive"))
      (node (ref "Q87") (pin "1") (pinfunction "G_1") (pintype "passive"))
      (node (ref "R332") (pin "2") (pinfunction "2_2") (pintype "passive"))
      (node (ref "R337") (pin "2") (pinfunction "2_2") (pintype "passive"))
    )
    (net (code "85") (name "Net-(Q88-D)") (class "Default")
      (node (ref "F30") (pin "2") (pintype "passive"))
      (node (ref "Q88") (pin "2") (pinfunction "D_2") (pintype "passive"))
    )
    (net (code "86") (name "Net-(Q88-G)") (class "Default")
      (node (ref "C236") (pin "2") (pinfunction "2_2") (pintype "passive"))
      (node (ref "Q88") (pin "1") (pinfunction "G_1") (pintype "passive"))
      (node (ref "R333") (pin "2") (pinfunction "2_2") (pintype "passive"))
      (node (ref "R338") (pin "2") (pinfunction "2_2") (pintype "passive"))
    )
    (net (code "87") (name "Net-(Q89-D)") (class "Default")
      (node (ref "F31") (pin "2") (pintype "passive"))
      (node (ref "Q89") (pin "2") (pinfunction "D_2") (pintype "passive"))
    )
    (net (code "88") (name "Net-(Q89-G)") (class "Default")
      (node (ref "C237") (pin "2") (pinfunction "2_2") (pintype "passive"))
      (node (ref "Q89") (pin "1") (pinfunction "G_1") (pintype "passive"))
      (node (ref "R334") (pin "2") (pinfunction "2_2") (pintype "passive"))
      (node (ref "R339") (pin "2") (pinfunction "2_2") (pintype "passive"))
    )
    (net (code "89") (name "Net-(Q90-D)") (class "Default")
      (node (ref "F32") (pin "2") (pintype "passive"))
      (node (ref "Q90") (pin "2") (pinfunction "D_2") (pintype "passive"))
    )
    (net (code "90") (name "Net-(Q90-G)") (class "Default")
      (node (ref "C238") (pin "2") (pinfunction "2_2") (pintype "passive"))
      (node (ref "Q90") (pin "1") (pinfunction "G_1") (pintype "passive"))
      (node (ref "R335") (pin "2") (pinfunction "2_2") (pintype "passive"))
      (node (ref "R340") (pin "2") (pinfunction "2_2") (pintype "passive"))
    )
    (net (code "91") (name "PF16+") (class "Default")
      (node (ref "C209") (pin "2") (pinfunction "2_2") (pintype "passive"))
      (node (ref "Q51") (pin "2") (pinfunction "G_2") (pintype "passive"))
      (node (ref "R256") (pin "2") (pinfunction "2_2") (pintype "passive"))
    )
    (net (code "92") (name "PF16-") (class "Default")
      (node (ref "R261") (pin "1") (pinfunction "1_1") (pintype "passive"))
      (node (ref "R271") (pin "1") (pinfunction "1_1") (pintype "passive"))
    )
    (net (code "93") (name "PF17+") (class "Default")
      (node (ref "C210") (pin "2") (pinfunction "2_2") (pintype "passive"))
      (node (ref "Q52") (pin "2") (pinfunction "G_2") (pintype "passive"))
      (node (ref "R257") (pin "2") (pinfunction "2_2") (pintype "passive"))
    )
    (net (code "94") (name "PF17-") (class "Default")
      (node (ref "R262") (pin "1") (pinfunction "1_1") (pintype "passive"))
      (node (ref "R272") (pin "1") (pinfunction "1_1") (pintype "passive"))
    )
    (net (code "95") (name "PF18+") (class "Default")
      (node (ref "C211") (pin "2") (pinfunction "2_2") (pintype "passive"))
      (node (ref "Q53") (pin "2") (pinfunction "G_2") (pintype "passive"))
      (node (ref "R258") (pin "2") (pinfunction "2_2") (pintype "passive"))
    )
    (net (code "96") (name "PF18-") (class "Default")
      (node (ref "R263") (pin "1") (pinfunction "1_1") (pintype "passive"))
      (node (ref "R273") (pin "1") (pinfunction "1_1") (pintype "passive"))
    )
    (net (code "97") (name "PF19+") (class "Default")
      (node (ref "C212") (pin "2") (pinfunction "2_2") (pintype "passive"))
      (node (ref "Q54") (pin "2") (pinfunction "G_2") (pintype "passive"))
      (node (ref "R259") (pin "2") (pinfunction "2_2") (pintype "passive"))
    )
    (net (code "98") (name "PF19-") (class "Default")
      (node (ref "R264") (pin "1") (pinfunction "1_1") (pintype "passive"))
      (node (ref "R274") (pin "1") (pinfunction "1_1") (pintype "passive"))
    )
    (net (code "99") (name "PF20+") (class "Default")
      (node (ref "C213") (pin "2") (pinfunction "2_2") (pintype "passive"))
      (node (ref "Q55") (pin "2") (pinfunction "G_2") (pintype "passive"))
      (node (ref "R260") (pin "2") (pinfunction "2_2") (pintype "passive"))
    )
    (net (code "100") (name "PF20-") (class "Default")
      (node (ref "R265") (pin "1") (pinfunction "1_1") (pintype "passive"))
      (node (ref "R275") (pin "1") (pinfunction "1_1") (pintype "passive"))
    )
    (net (code "101") (name "PF21+") (class "Default")
      (node (ref "C219") (pin "2") (pinfunction "2_2") (pintype "passive"))
      (node (ref "Q66") (pin "2") (pinfunction "G_2") (pintype "passive"))
      (node (ref "R291") (pin "2") (pinfunction "2_2") (pintype "passive"))
    )
    (net (code "102") (name "PF21-") (class "Default")
      (node (ref "R296") (pin "1") (pinfunction "1_1") (pintype "passive"))
      (node (ref "R306") (pin "1") (pinfunction "1_1") (pintype "passive"))
    )
    (net (code "103") (name "PF22+") (class "Default")
      (node (ref "C220") (pin "2") (pinfunction "2_2") (pintype "passive"))
      (node (ref "Q67") (pin "2") (pinfunction "G_2") (pintype "passive"))
      (node (ref "R292") (pin "2") (pinfunction "2_2") (pintype "passive"))
    )
    (net (code "104") (name "PF22-") (class "Default")
      (node (ref "R297") (pin "1") (pinfunction "1_1") (pintype "passive"))
      (node (ref "R307") (pin "1") (pinfunction "1_1") (pintype "passive"))
    )
    (net (code "105") (name "PF23+") (class "Default")
      (node (ref "C221") (pin "2") (pinfunction "2_2") (pintype "passive"))
      (node (ref "Q68") (pin "2") (pinfunction "G_2") (pintype "passive"))
      (node (ref "R293") (pin "2") (pinfunction "2_2") (pintype "passive"))
    )
    (net (code "106") (name "PF23-") (class "Default")
      (node (ref "R298") (pin "1") (pinfunction "1_1") (pintype "passive"))
      (node (ref "R308") (pin "1") (pinfunction "1_1") (pintype "passive"))
    )
    (net (code "107") (name "PF24+") (class "Default")
      (node (ref "C222") (pin "2") (pinfunction "2_2") (pintype "passive"))
      (node (ref "Q69") (pin "2") (pinfunction "G_2") (pintype "passive"))
      (node (ref "R294") (pin "2") (pinfunction "2_2") (pintype "passive"))
    )
    (net (code "108") (name "PF24-") (class "Default")
      (node (ref "R299") (pin "1") (pinfunction "1_1") (pintype "passive"))
      (node (ref "R309") (pin "1") (pinfunction "1_1") (pintype "passive"))
    )
    (net (code "109") (name "PF25+") (class "Default")
      (node (ref "C223") (pin "2") (pinfunction "2_2") (pintype "passive"))
      (node (ref "Q70") (pin "2") (pinfunction "G_2") (pintype "passive"))
      (node (ref "R295") (pin "2") (pinfunction "2_2") (pintype "passive"))
    )
    (net (code "110") (name "PF25-") (class "Default")
      (node (ref "R300") (pin "1") (pinfunction "1_1") (pintype "passive"))
      (node (ref "R310") (pin "1") (pinfunction "1_1") (pintype "passive"))
    )
    (net (code "111") (name "PF26+") (class "Default")
      (node (ref "C229") (pin "2") (pinfunction "2_2") (pintype "passive"))
      (node (ref "Q81") (pin "2") (pinfunction "G_2") (pintype "passive"))
      (node (ref "R326") (pin "2") (pinfunction "2_2") (pintype "passive"))
    )
    (net (code "112") (name "PF26-") (class "Default")
      (node (ref "R331") (pin "1") (pinfunction "1_1") (pintype "passive"))
      (node (ref "R341") (pin "1") (pinfunction "1_1") (pintype "passive"))
    )
    (net (code "113") (name "PF27+") (class "Default")
      (node (ref "C230") (pin "2") (pinfunction "2_2") (pintype "passive"))
      (node (ref "Q82") (pin "2") (pinfunction "G_2") (pintype "passive"))
      (node (ref "R327") (pin "2") (pinfunction "2_2") (pintype "passive"))
    )
    (net (code "114") (name "PF27-") (class "Default")
      (node (ref "R332") (pin "1") (pinfunction "1_1") (pintype "passive"))
      (node (ref "R342") (pin "1") (pinfunction "1_1") (pintype "passive"))
    )
    (net (code "115") (name "PF28+") (class "Default")
      (node (ref "C231") (pin "2") (pinfunction "2_2") (pintype "passive"))
      (node (ref "Q83") (pin "2") (pinfunction "G_2") (pintype "passive"))
      (node (ref "R328") (pin "2") (pinfunction "2_2") (pintype "passive"))
    )
    (net (code "116") (name "PF28-") (class "Default")
      (node (ref "R333") (pin "1") (pinfunction "1_1") (pintype "passive"))
      (node (ref "R343") (pin "1") (pinfunction "1_1") (pintype "passive"))
    )
    (net (code "117") (name "PF29+") (class "Default")
      (node (ref "C232") (pin "2") (pinfunction "2_2") (pintype "passive"))
      (node (ref "Q84") (pin "2") (pinfunction "G_2") (pintype "passive"))
      (node (ref "R329") (pin "2") (pinfunction "2_2") (pintype "passive"))
    )
    (net (code "118") (name "PF29-") (class "Default")
      (node (ref "R334") (pin "1") (pinfunction "1_1") (pintype "passive"))
      (node (ref "R344") (pin "1") (pinfunction "1_1") (pintype "passive"))
    )
    (net (code "119") (name "PF30+") (class "Default")
      (node (ref "C233") (pin "2") (pinfunction "2_2") (pintype "passive"))
      (node (ref "Q85") (pin "2") (pinfunction "G_2") (pintype "passive"))
      (node (ref "R330") (pin "2") (pinfunction "2_2") (pintype "passive"))
    )
    (net (code "120") (name "PF30-") (class "Default")
      (node (ref "R335") (pin "1") (pinfunction "1_1") (pintype "passive"))
      (node (ref "R345") (pin "1") (pinfunction "1_1") (pintype "passive"))
    )
    (net (code "121") (name "PGND") (class "Default")
      (node (ref "C209") (pin "1") (pinfunction "1_1") (pintype "passive"))
      (node (ref "C210") (pin "1") (pinfunction "1_1") (pintype "passive"))
      (node (ref "C211") (pin "1") (pinfunction "1_1") (pintype "passive"))
      (node (ref "C212") (pin "1") (pinfunction "1_1") (pintype "passive"))
      (node (ref "C213") (pin "1") (pinfunction "1_1") (pintype "passive"))
      (node (ref "C214") (pin "1") (pinfunction "1_1") (pintype "passive"))
      (node (ref "C215") (pin "1") (pinfunction "1_1") (pintype "passive"))
      (node (ref "C216") (pin "1") (pinfunction "1_1") (pintype "passive"))
      (node (ref "C217") (pin "1") (pinfunction "1_1") (pintype "passive"))
      (node (ref "C218") (pin "1") (pinfunction "1_1") (pintype "passive"))
      (node (ref "C219") (pin "1") (pinfunction "1_1") (pintype "passive"))
      (node (ref "C220") (pin "1") (pinfunction "1_1") (pintype "passive"))
      (node (ref "C221") (pin "1") (pinfunction "1_1") (pintype "passive"))
      (node (ref "C222") (pin "1") (pinfunction "1_1") (pintype "passive"))
      (node (ref "C223") (pin "1") (pinfunction "1_1") (pintype "passive"))
      (node (ref "C224") (pin "1") (pinfunction "1_1") (pintype "passive"))
      (node (ref "C225") (pin "1") (pinfunction "1_1") (pintype "passive"))
      (node (ref "C226") (pin "1") (pinfunction "1_1") (pintype "passive"))
      (node (ref "C227") (pin "1") (pinfunction "1_1") (pintype "passive"))
      (node (ref "C228") (pin "1") (pinfunction "1_1") (pintype "passive"))
      (node (ref "C229") (pin "1") (pinfunction "1_1") (pintype "passive"))
      (node (ref "C230") (pin "1") (pinfunction "1_1") (pintype "passive"))
      (node (ref "C231") (pin "1") (pinfunction "1_1") (pintype "passive"))
      (node (ref "C232") (pin "1") (pinfunction "1_1") (pintype "passive"))
      (node (ref "C233") (pin "1") (pinfunction "1_1") (pintype "passive"))
      (node (ref "C234") (pin "1") (pinfunction "1_1") (pintype "passive"))
      (node (ref "C235") (pin "1") (pinfunction "1_1") (pintype "passive"))
      (node (ref "C236") (pin "1") (pinfunction "1_1") (pintype "passive"))
      (node (ref "C237") (pin "1") (pinfunction "1_1") (pintype "passive"))
      (node (ref "C238") (pin "1") (pinfunction "1_1") (pintype "passive"))
      (node (ref "Q51") (pin "3") (pinfunction "S_3") (pintype "passive"))
      (node (ref "Q52") (pin "3") (pinfunction "S_3") (pintype "passive"))
      (node (ref "Q53") (pin "3") (pinfunction "S_3") (pintype "passive"))
      (node (ref "Q54") (pin "3") (pinfunction "S_3") (pintype "passive"))
      (node (ref "Q55") (pin "3") (pinfunction "S_3") (pintype "passive"))
      (node (ref "Q56") (pin "3") (pinfunction "S_3") (pintype "passive"))
      (node (ref "Q57") (pin "3") (pinfunction "S_3") (pintype "passive"))
      (node (ref "Q58") (pin "3") (pinfunction "S_3") (pintype "passive"))
      (node (ref "Q59") (pin "3") (pinfunction "S_3") (pintype "passive"))
      (node (ref "Q60") (pin "3") (pinfunction "S_3") (pintype "passive"))
      (node (ref "Q66") (pin "3") (pinfunction "S_3") (pintype "passive"))
      (node (ref "Q67") (pin "3") (pinfunction "S_3") (pintype "passive"))
      (node (ref "Q68") (pin "3") (pinfunction "S_3") (pintype "passive"))
      (node (ref "Q69") (pin "3") (pinfunction "S_3") (pintype "passive"))
      (node (ref "Q70") (pin "3") (pinfunction "S_3") (pintype "passive"))
      (node (ref "Q71") (pin "3") (pinfunction "S_3") (pintype "passive"))
      (node (ref "Q72") (pin "3") (pinfunction "S_3") (pintype "passive"))
      (node (ref "Q73") (pin "3") (pinfunction "S_3") (pintype "passive"))
      (node (ref "Q74") (pin "3") (pinfunction "S_3") (pintype "passive"))
      (node (ref "Q75") (pin "3") (pinfunction "S_3") (pintype "passive"))
      (node (ref "Q81") (pin "3") (pinfunction "S_3") (pintype "passive"))
      (node (ref "Q82") (pin "3") (pinfunction "S_3") (pintype "passive"))
      (node (ref "Q83") (pin "3") (pinfunction "S_3") (pintype "passive"))
      (node (ref "Q84") (pin "3") (pinfunction "S_3") (pintype "passive"))
      (node (ref "Q85") (pin "3") (pinfunction "S_3") (pintype "passive"))
      (node (ref "Q86") (pin "3") (pinfunction "S_3") (pintype "passive"))
      (node (ref "Q87") (pin "3") (pinfunction "S_3") (pintype "passive"))
      (node (ref "Q88") (pin "3") (pinfunction "S_3") (pintype "passive"))
      (node (ref "Q89") (pin "3") (pinfunction "S_3") (pintype "passive"))
      (node (ref "Q90") (pin "3") (pinfunction "S_3") (pintype "passive"))
      (node (ref "R256") (pin "1") (pinfunction "1_1") (pintype "passive"))
      (node (ref "R257") (pin "1") (pinfunction "1_1") (pintype "passive"))
      (node (ref "R258") (pin "1") (pinfunction "1_1") (pintype "passive"))
      (node (ref "R259") (pin "1") (pinfunction "1_1") (pintype "passive"))
      (node (ref "R260") (pin "1") (pinfunction "1_1") (pintype "passive"))
      (node (ref "R266") (pin "1") (pinfunction "1_1") (pintype "passive"))
      (node (ref "R267") (pin "1") (pinfunction "1_1") (pintype "passive"))
      (node (ref "R268") (pin "1") (pinfunction "1_1") (pintype "passive"))
      (node (ref "R269") (pin "1") (pinfunction "1_1") (pintype "passive"))
      (node (ref "R270") (pin "1") (pinfunction "1_1") (pintype "passive"))
      (node (ref "R271") (pin "2") (pinfunction "2_2") (pintype "passive"))
      (node (ref "R272") (pin "2") (pinfunction "2_2") (pintype "passive"))
      (node (ref "R273") (pin "2") (pinfunction "2_2") (pintype "passive"))
      (node (ref "R274") (pin "2") (pinfunction "2_2") (pintype "passive"))
      (node (ref "R275") (pin "2") (pinfunction "2_2") (pintype "passive"))
      (node (ref "R291") (pin "1") (pinfunction "1_1") (pintype "passive"))
      (node (ref "R292") (pin "1") (pinfunction "1_1") (pintype "passive"))
      (node (ref "R293") (pin "1") (pinfunction "1_1") (pintype "passive"))
      (node (ref "R294") (pin "1") (pinfunction "1_1") (pintype "passive"))
      (node (ref "R295") (pin "1") (pinfunction "1_1") (pintype "passive"))
      (node (ref "R301") (pin "1") (pinfunction "1_1") (pintype "passive"))
      (node (ref "R302") (pin "1") (pinfunction "1_1") (pintype "passive"))
      (node (ref "R303") (pin "1") (pinfunction "1_1") (pintype "passive"))
      (node (ref "R304") (pin "1") (pinfunction "1_1") (pintype "passive"))
      (node (ref "R305") (pin "1") (pinfunction "1_1") (pintype "passive"))
      (node (ref "R306") (pin "2") (pinfunction "2_2") (pintype "passive"))
      (node (ref "R307") (pin "2") (pinfunction "2_2") (pintype "passive"))
      (node (ref "R308") (pin "2") (pinfunction "2_2") (pintype "passive"))
      (node (ref "R309") (pin "2") (pinfunction "2_2") (pintype "passive"))
      (node (ref "R310") (pin "2") (pinfunction "2_2") (pintype "passive"))
      (node (ref "R326") (pin "1") (pinfunction "1_1") (pintype "passive"))
      (node (ref "R327") (pin "1") (pinfunction "1_1") (pintype "passive"))
      (node (ref "R328") (pin "1") (pinfunction "1_1") (pintype "passive"))
      (node (ref "R329") (pin "1") (pinfunction "1_1") (pintype "passive"))
      (node (ref "R330") (pin "1") (pinfunction "1_1") (pintype "passive"))
      (node (ref "R336") (pin "1") (pinfunction "1_1") (pintype "passive"))
      (node (ref "R337") (pin "1") (pinfunction "1_1") (pintype "passive"))
      (node (ref "R338") (pin "1") (pinfunction "1_1") (pintype "passive"))
      (node (ref "R339") (pin "1") (pinfunction "1_1") (pintype "passive"))
      (node (ref "R340") (pin "1") (pinfunction "1_1") (pintype "passive"))
      (node (ref "R341") (pin "2") (pinfunction "2_2") (pintype "passive"))
      (node (ref "R342") (pin "2") (pinfunction "2_2") (pintype "passive"))
      (node (ref "R343") (pin "2") (pinfunction "2_2") (pintype "passive"))
      (node (ref "R344") (pin "2") (pinfunction "2_2") (pintype "passive"))
      (node (ref "R345") (pin "2") (pinfunction "2_2") (pintype "passive"))
    )
    (net (code "122") (name "PHIGH") (class "Default")
      (node (ref "D103") (pin "1") (pinfunction "1_1") (pintype "passive"))
      (node (ref "D104") (pin "1") (pinfunction "1_1") (pintype "passive"))
      (node (ref "D105") (pin "1") (pinfunction "1_1") (pintype "passive"))
      (node (ref "D106") (pin "1") (pinfunction "1_1") (pintype "passive"))
      (node (ref "D107") (pin "1") (pinfunction "1_1") (pintype "passive"))
      (node (ref "D83") (pin "1") (pinfunction "1_1") (pintype "passive"))
      (node (ref "D84") (pin "1") (pinfunction "1_1") (pintype "passive"))
      (node (ref "D85") (pin "1") (pinfunction "1_1") (pintype "passive"))
      (node (ref "D86") (pin "1") (pinfunction "1_1") (pintype "passive"))
      (node (ref "D87") (pin "1") (pinfunction "1_1") (pintype "passive"))
      (node (ref "D93") (pin "1") (pinfunction "1_1") (pintype "passive"))
      (node (ref "D94") (pin "1") (pinfunction "1_1") (pintype "passive"))
      (node (ref "D95") (pin "1") (pinfunction "1_1") (pintype "passive"))
      (node (ref "D96") (pin "1") (pinfunction "1_1") (pintype "passive"))
      (node (ref "D97") (pin "1") (pinfunction "1_1") (pintype "passive"))
      (node (ref "Q46") (pin "3") (pinfunction "S_3") (pintype "passive"))
      (node (ref "Q47") (pin "3") (pinfunction "S_3") (pintype "passive"))
      (node (ref "Q48") (pin "3") (pinfunction "S_3") (pintype "passive"))
      (node (ref "Q49") (pin "3") (pinfunction "S_3") (pintype "passive"))
      (node (ref "Q50") (pin "3") (pinfunction "S_3") (pintype "passive"))
      (node (ref "Q61") (pin "3") (pinfunction "S_3") (pintype "passive"))
      (node (ref "Q62") (pin "3") (pinfunction "S_3") (pintype "passive"))
      (node (ref "Q63") (pin "3") (pinfunction "S_3") (pintype "passive"))
      (node (ref "Q64") (pin "3") (pinfunction "S_3") (pintype "passive"))
      (node (ref "Q65") (pin "3") (pinfunction "S_3") (pintype "passive"))
      (node (ref "Q76") (pin "3") (pinfunction "S_3") (pintype "passive"))
      (node (ref "Q77") (pin "3") (pinfunction "S_3") (pintype "passive"))
      (node (ref "Q78") (pin "3") (pinfunction "S_3") (pintype "passive"))
      (node (ref "Q79") (pin "3") (pinfunction "S_3") (pintype "passive"))
      (node (ref "Q80") (pin "3") (pinfunction "S_3") (pintype "passive"))
      (node (ref "R241") (pin "2") (pinfunction "2_2") (pintype "passive"))
      (node (ref "R242") (pin "2") (pinfunction "2_2") (pintype "passive"))
      (node (ref "R243") (pin "2") (pinfunction "2_2") (pintype "passive"))
      (node (ref "R244") (pin "2") (pinfunction "2_2") (pintype "passive"))
      (node (ref "R245") (pin "2") (pinfunction "2_2") (pintype "passive"))
      (node (ref "R246") (pin "2") (pinfunction "2_2") (pintype "passive"))
      (node (ref "R247") (pin "2") (pinfunction "2_2") (pintype "passive"))
      (node (ref "R248") (pin "2") (pinfunction "2_2") (pintype "passive"))
      (node (ref "R249") (pin "2") (pinfunction "2_2") (pintype "passive"))
      (node (ref "R250") (pin "2") (pinfunction "2_2") (pintype "passive"))
      (node (ref "R276") (pin "2") (pinfunction "2_2") (pintype "passive"))
      (node (ref "R277") (pin "2") (pinfunction "2_2") (pintype "passive"))
      (node (ref "R278") (pin "2") (pinfunction "2_2") (pintype "passive"))
      (node (ref "R279") (pin "2") (pinfunction "2_2") (pintype "passive"))
      (node (ref "R280") (pin "2") (pinfunction "2_2") (pintype "passive"))
      (node (ref "R281") (pin "2") (pinfunction "2_2") (pintype "passive"))
      (node (ref "R282") (pin "2") (pinfunction "2_2") (pintype "passive"))
      (node (ref "R283") (pin "2") (pinfunction "2_2") (pintype "passive"))
      (node (ref "R284") (pin "2") (pinfunction "2_2") (pintype "passive"))
      (node (ref "R285") (pin "2") (pinfunction "2_2") (pintype "passive"))
      (node (ref "R311") (pin "2") (pinfunction "2_2") (pintype "passive"))
      (node (ref "R312") (pin "2") (pinfunction "2_2") (pintype "passive"))
      (node (ref "R313") (pin "2") (pinfunction "2_2") (pintype "passive"))
      (node (ref "R314") (pin "2") (pinfunction "2_2") (pintype "passive"))
      (node (ref "R315") (pin "2") (pinfunction "2_2") (pintype "passive"))
      (node (ref "R316") (pin "2") (pinfunction "2_2") (pintype "passive"))
      (node (ref "R317") (pin "2") (pinfunction "2_2") (pintype "passive"))
      (node (ref "R318") (pin "2") (pinfunction "2_2") (pintype "passive"))
      (node (ref "R319") (pin "2") (pinfunction "2_2") (pintype "passive"))
      (node (ref "R320") (pin "2") (pinfunction "2_2") (pintype "passive"))
    )
    (net (code "123") (name "PLOW") (class "Default")
      (node (ref "D100") (pin "2") (pinfunction "2_2") (pintype "passive"))
      (node (ref "D101") (pin "2") (pinfunction "2_2") (pintype "passive"))
      (node (ref "D102") (pin "2") (pinfunction "2_2") (pintype "passive"))
      (node (ref "D108") (pin "2") (pinfunction "2_2") (pintype "passive"))
      (node (ref "D109") (pin "2") (pinfunction "2_2") (pintype "passive"))
      (node (ref "D110") (pin "2") (pinfunction "2_2") (pintype "passive"))
      (node (ref "D111") (pin "2") (pinfunction "2_2") (pintype "passive"))
      (node (ref "D112") (pin "2") (pinfunction "2_2") (pintype "passive"))
      (node (ref "D88") (pin "2") (pinfunction "2_2") (pintype "passive"))
      (node (ref "D89") (pin "2") (pinfunction "2_2") (pintype "passive"))
      (node (ref "D90") (pin "2") (pinfunction "2_2") (pintype "passive"))
      (node (ref "D91") (pin "2") (pinfunction "2_2") (pintype "passive"))
      (node (ref "D92") (pin "2") (pinfunction "2_2") (pintype "passive"))
      (node (ref "D98") (pin "2") (pinfunction "2_2") (pintype "passive"))
      (node (ref "D99") (pin "2") (pinfunction "2_2") (pintype "passive"))
    )
  )
)
